# rev_k_v36.net
KiCad netlist of a schematic drawn in EAGLE
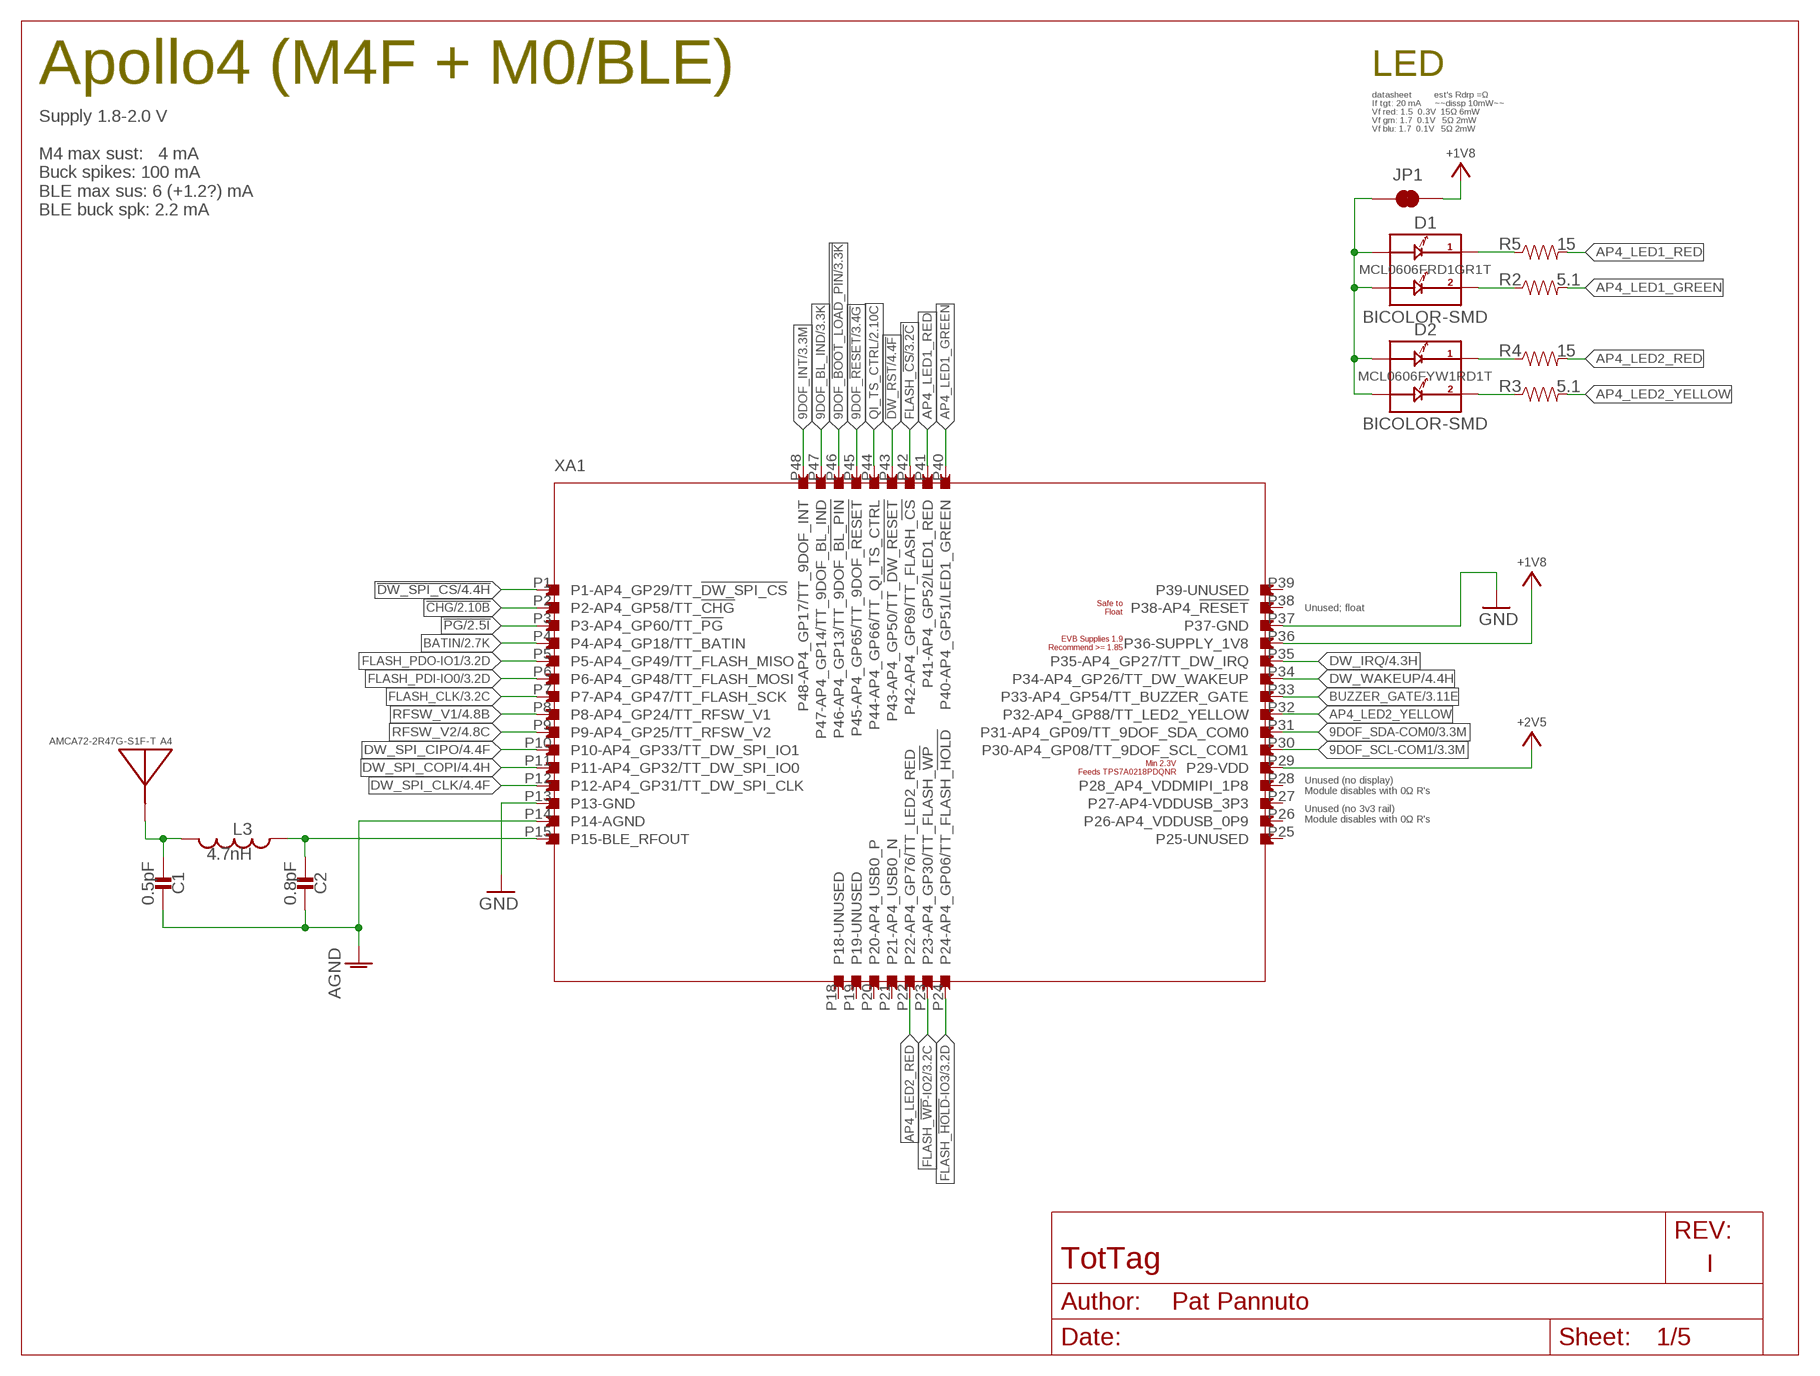
[diagram p0: schematic, sheet 1]
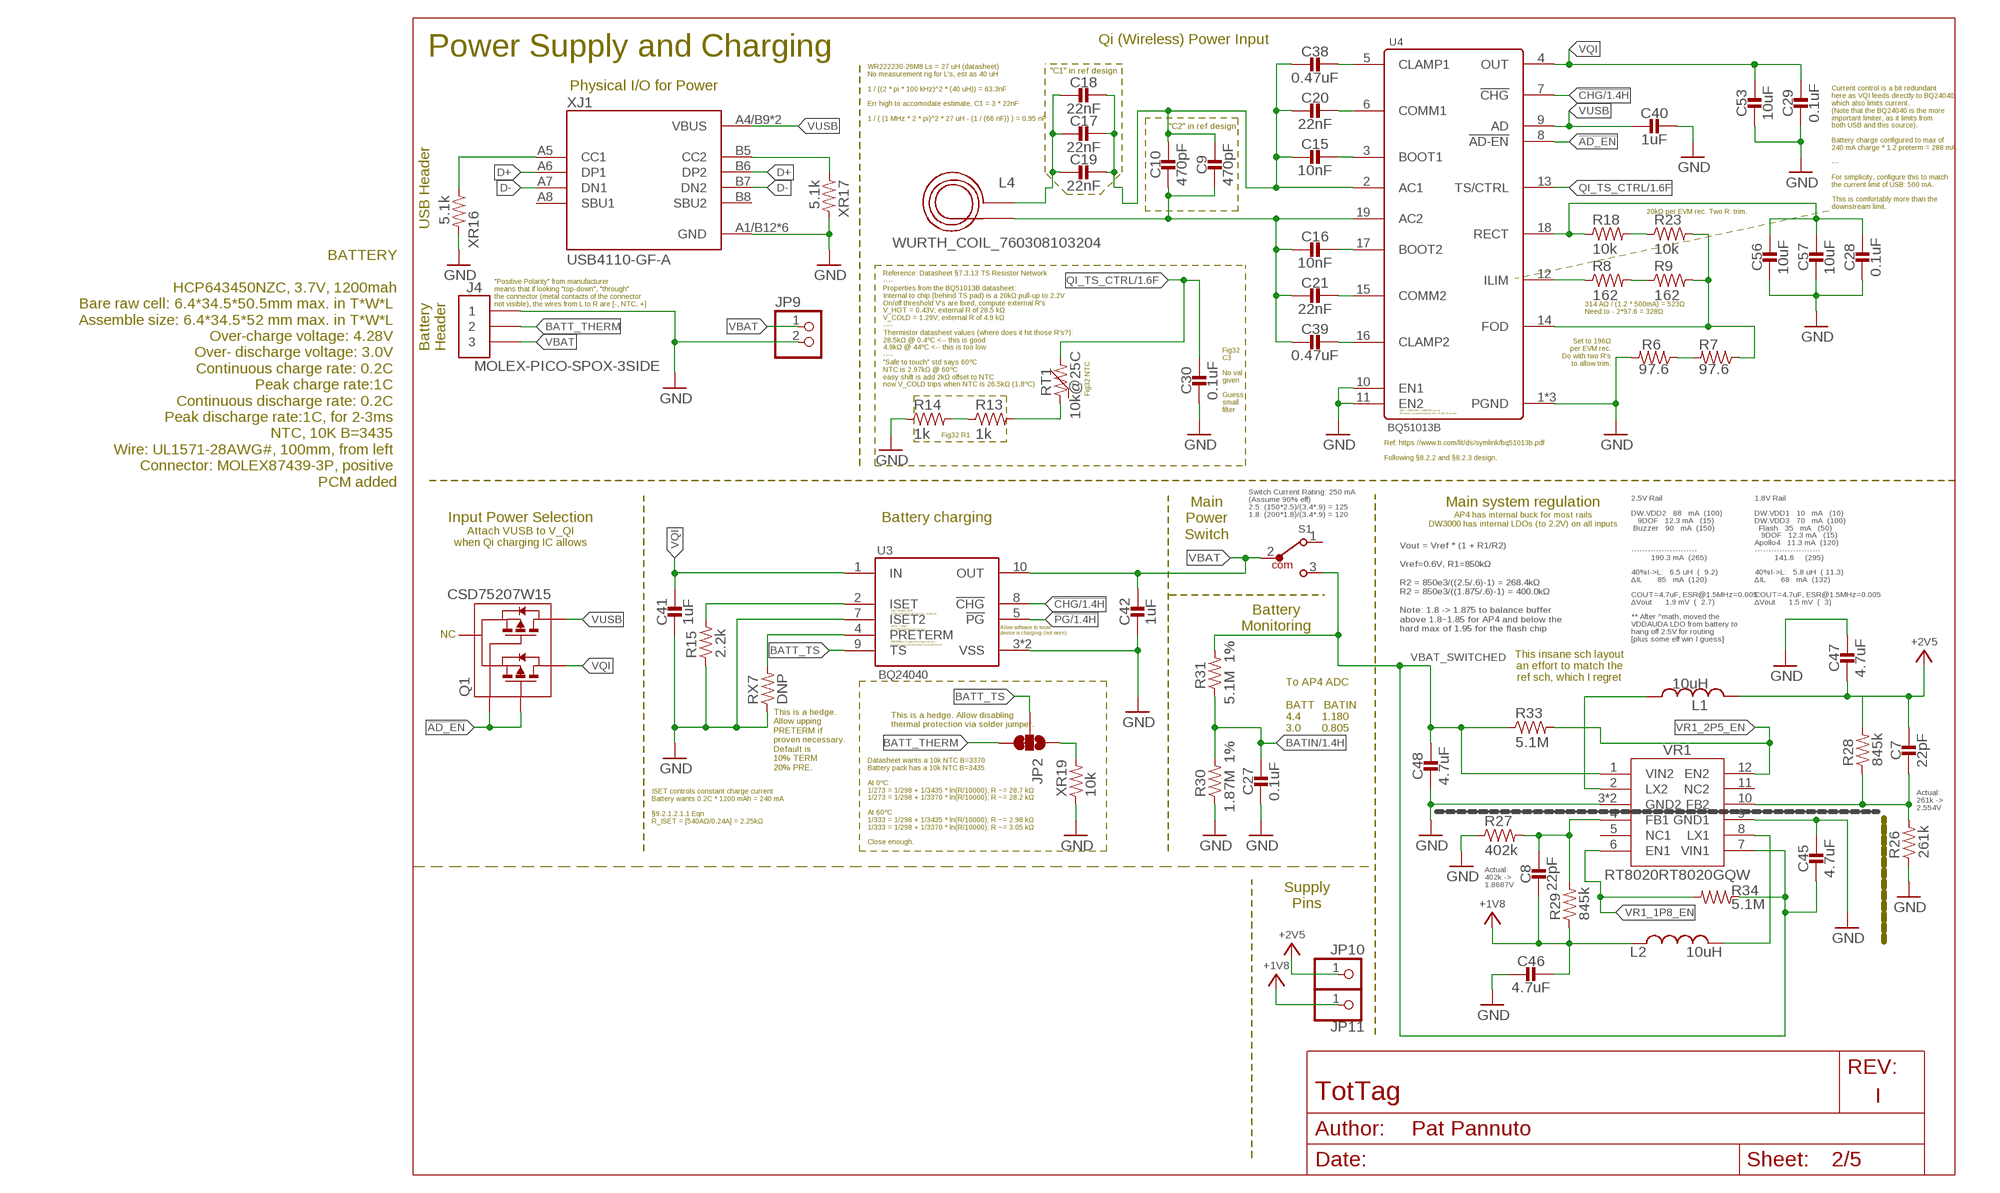
[diagram p1: schematic, sheet 2]
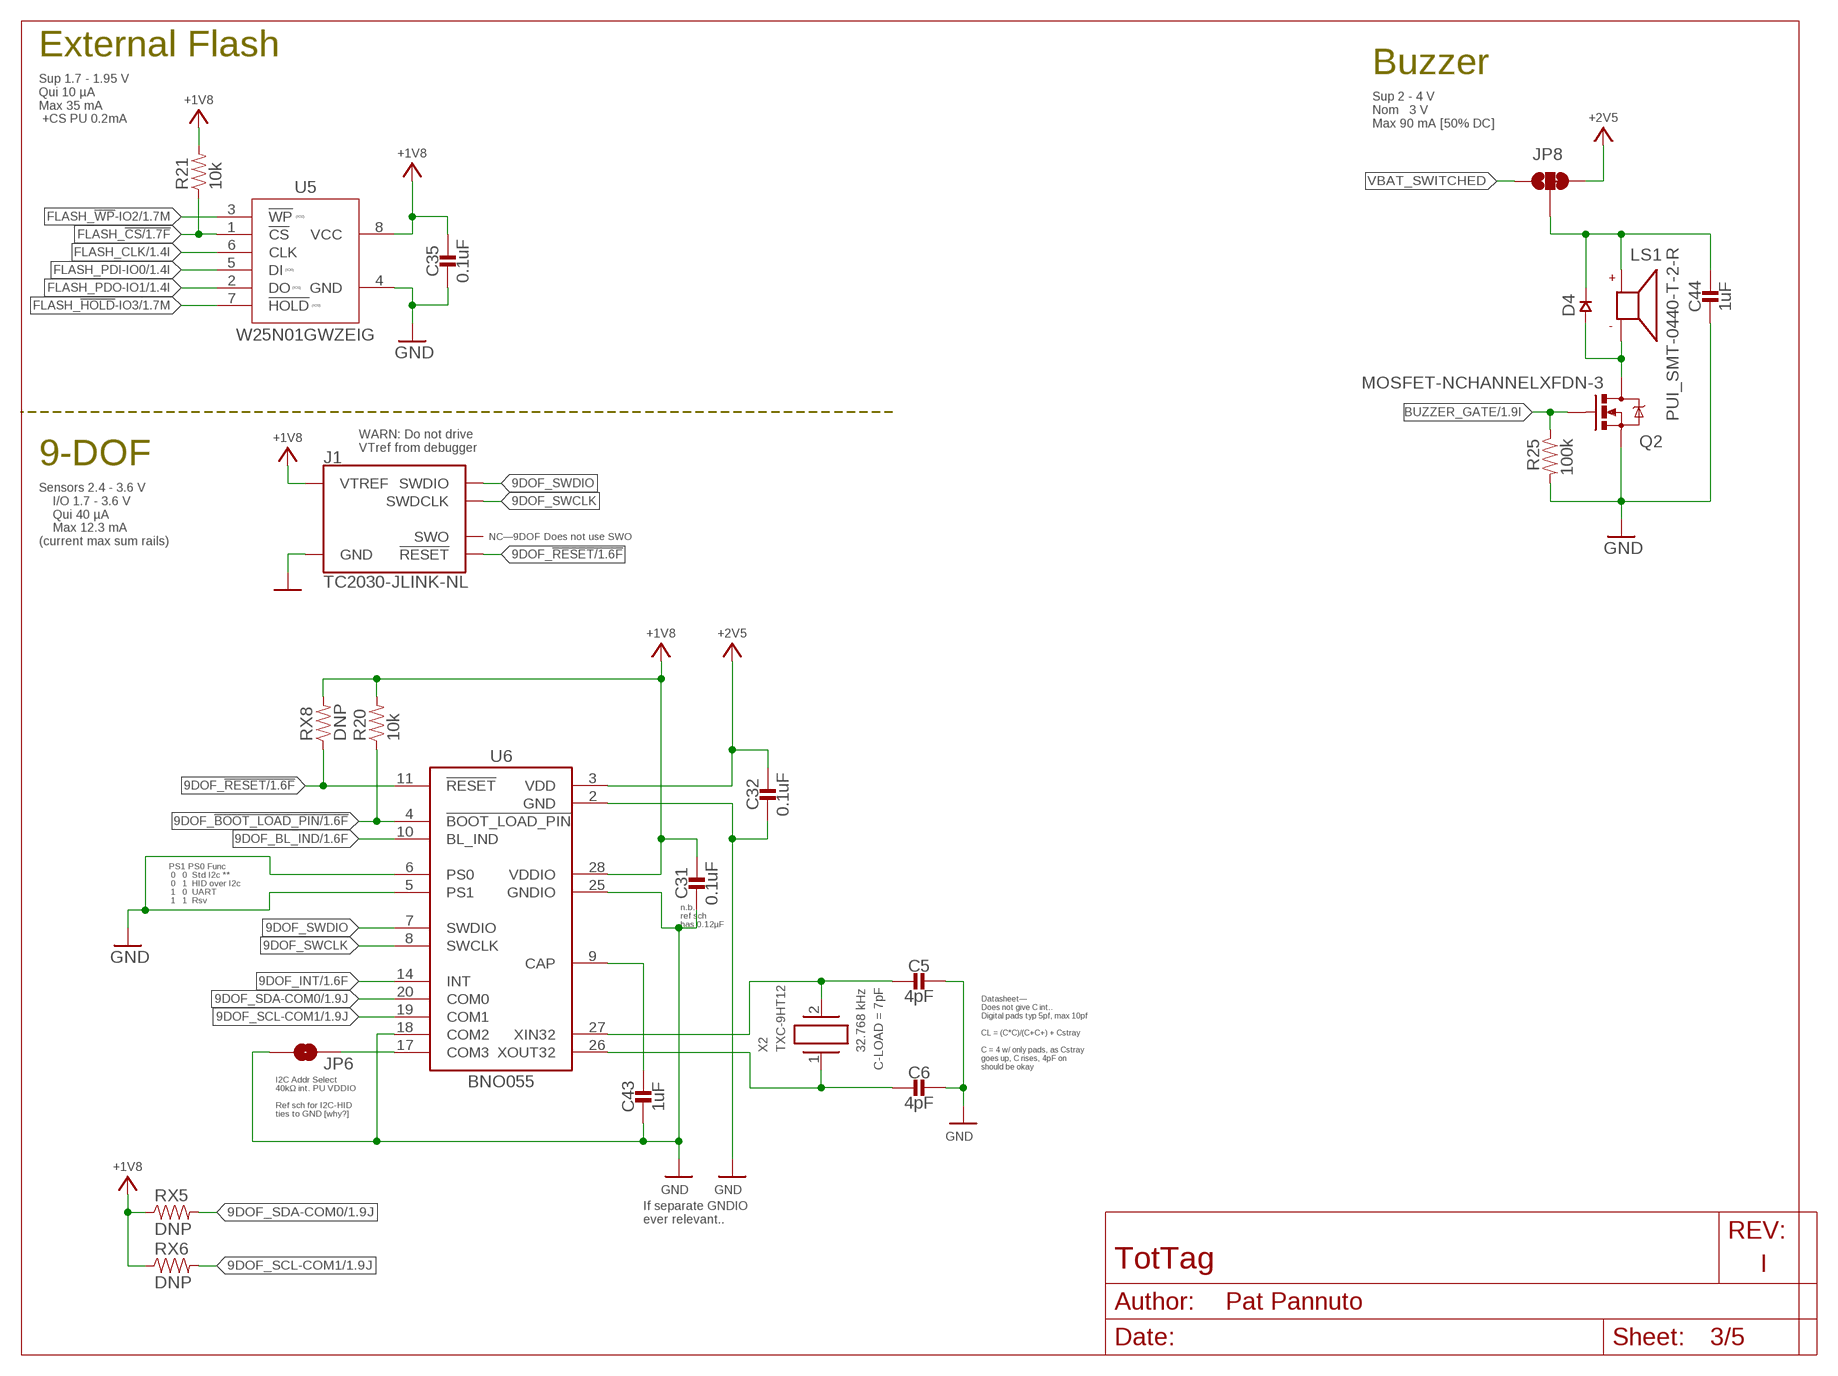
[diagram p2: schematic, sheet 3]
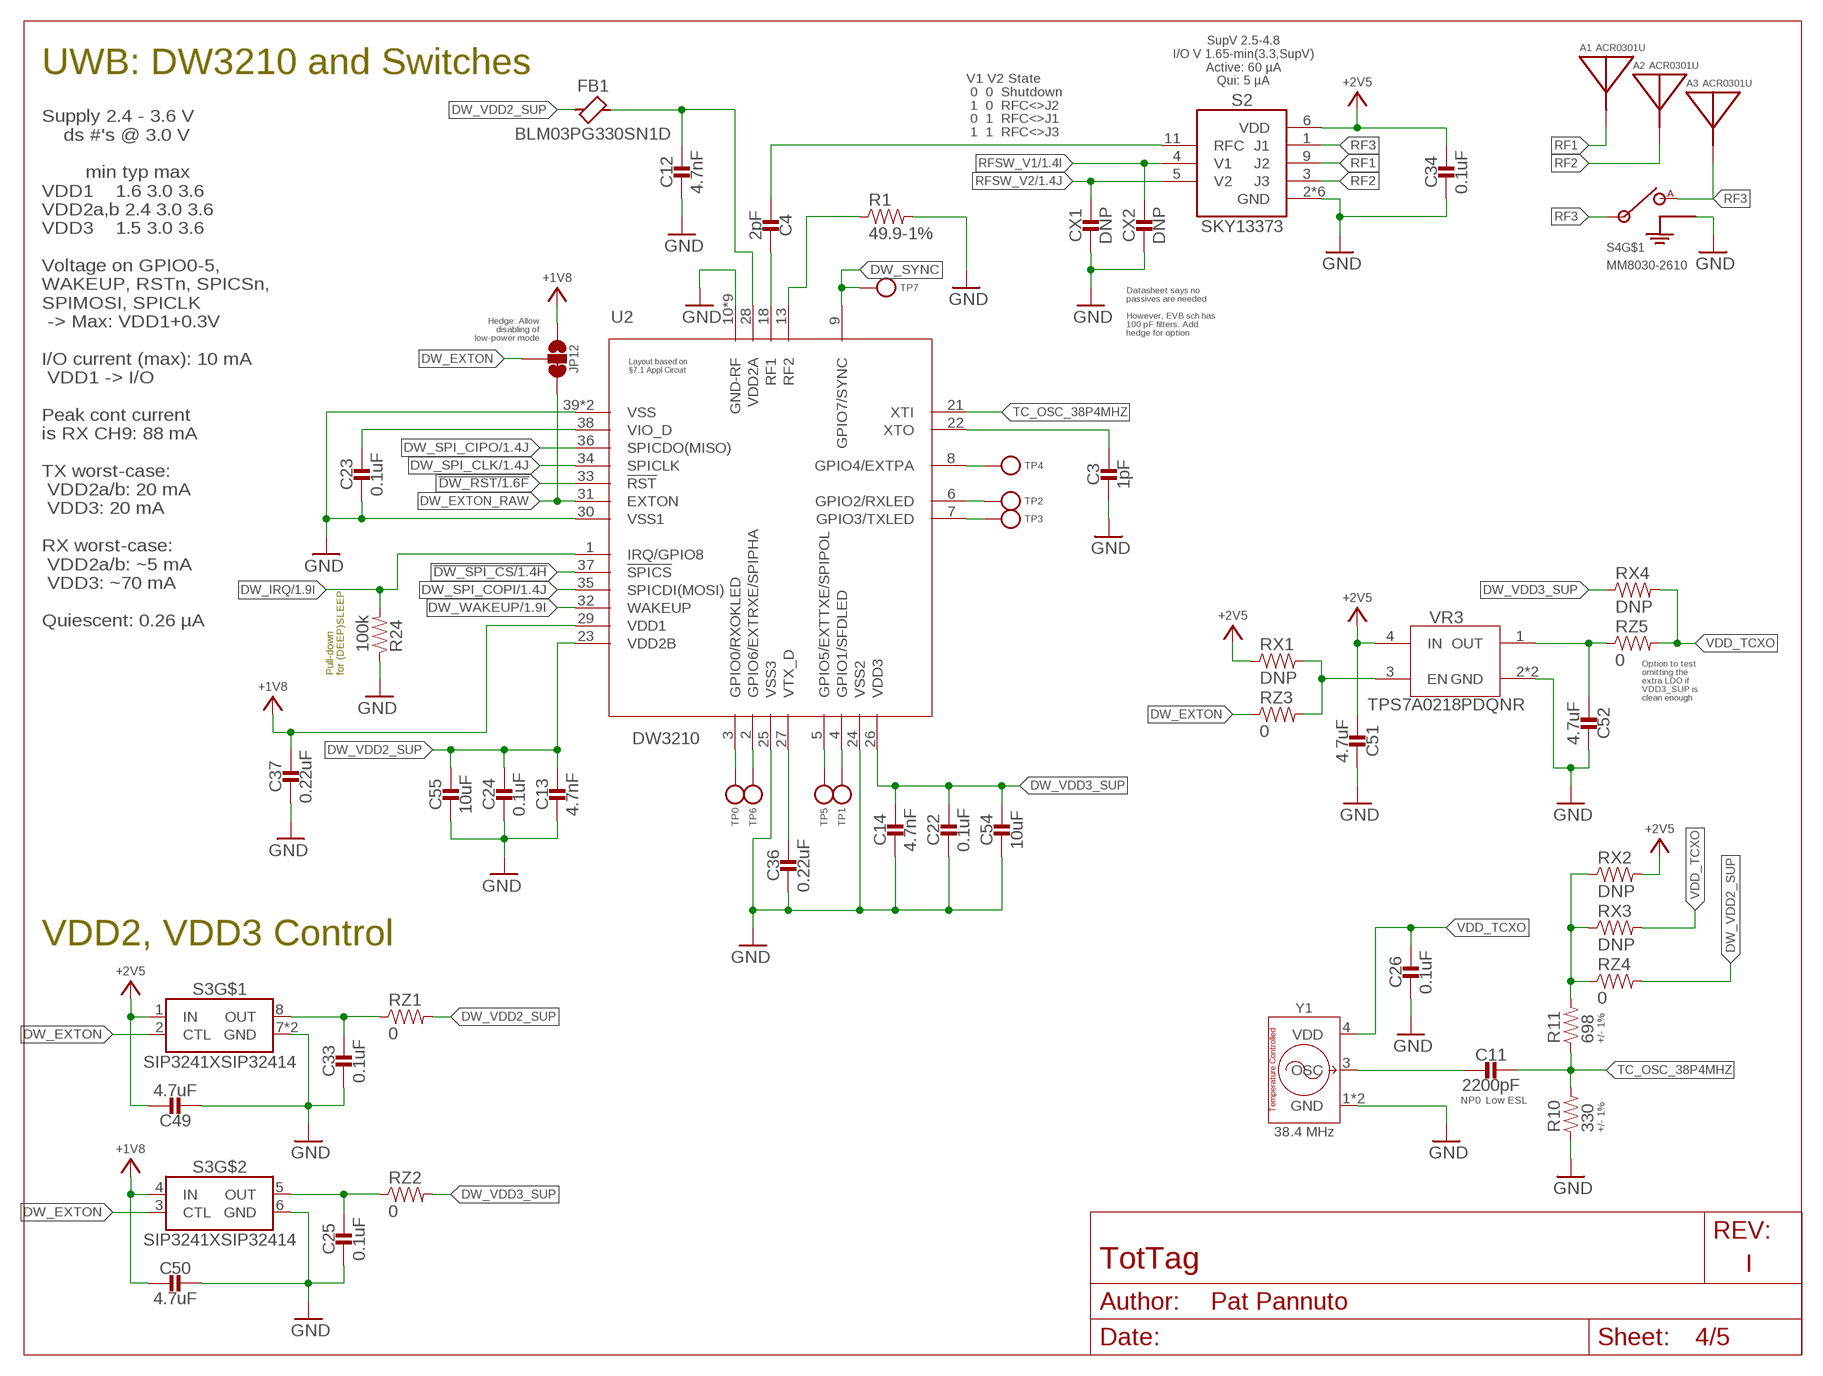
[diagram p3: schematic, sheet 4]
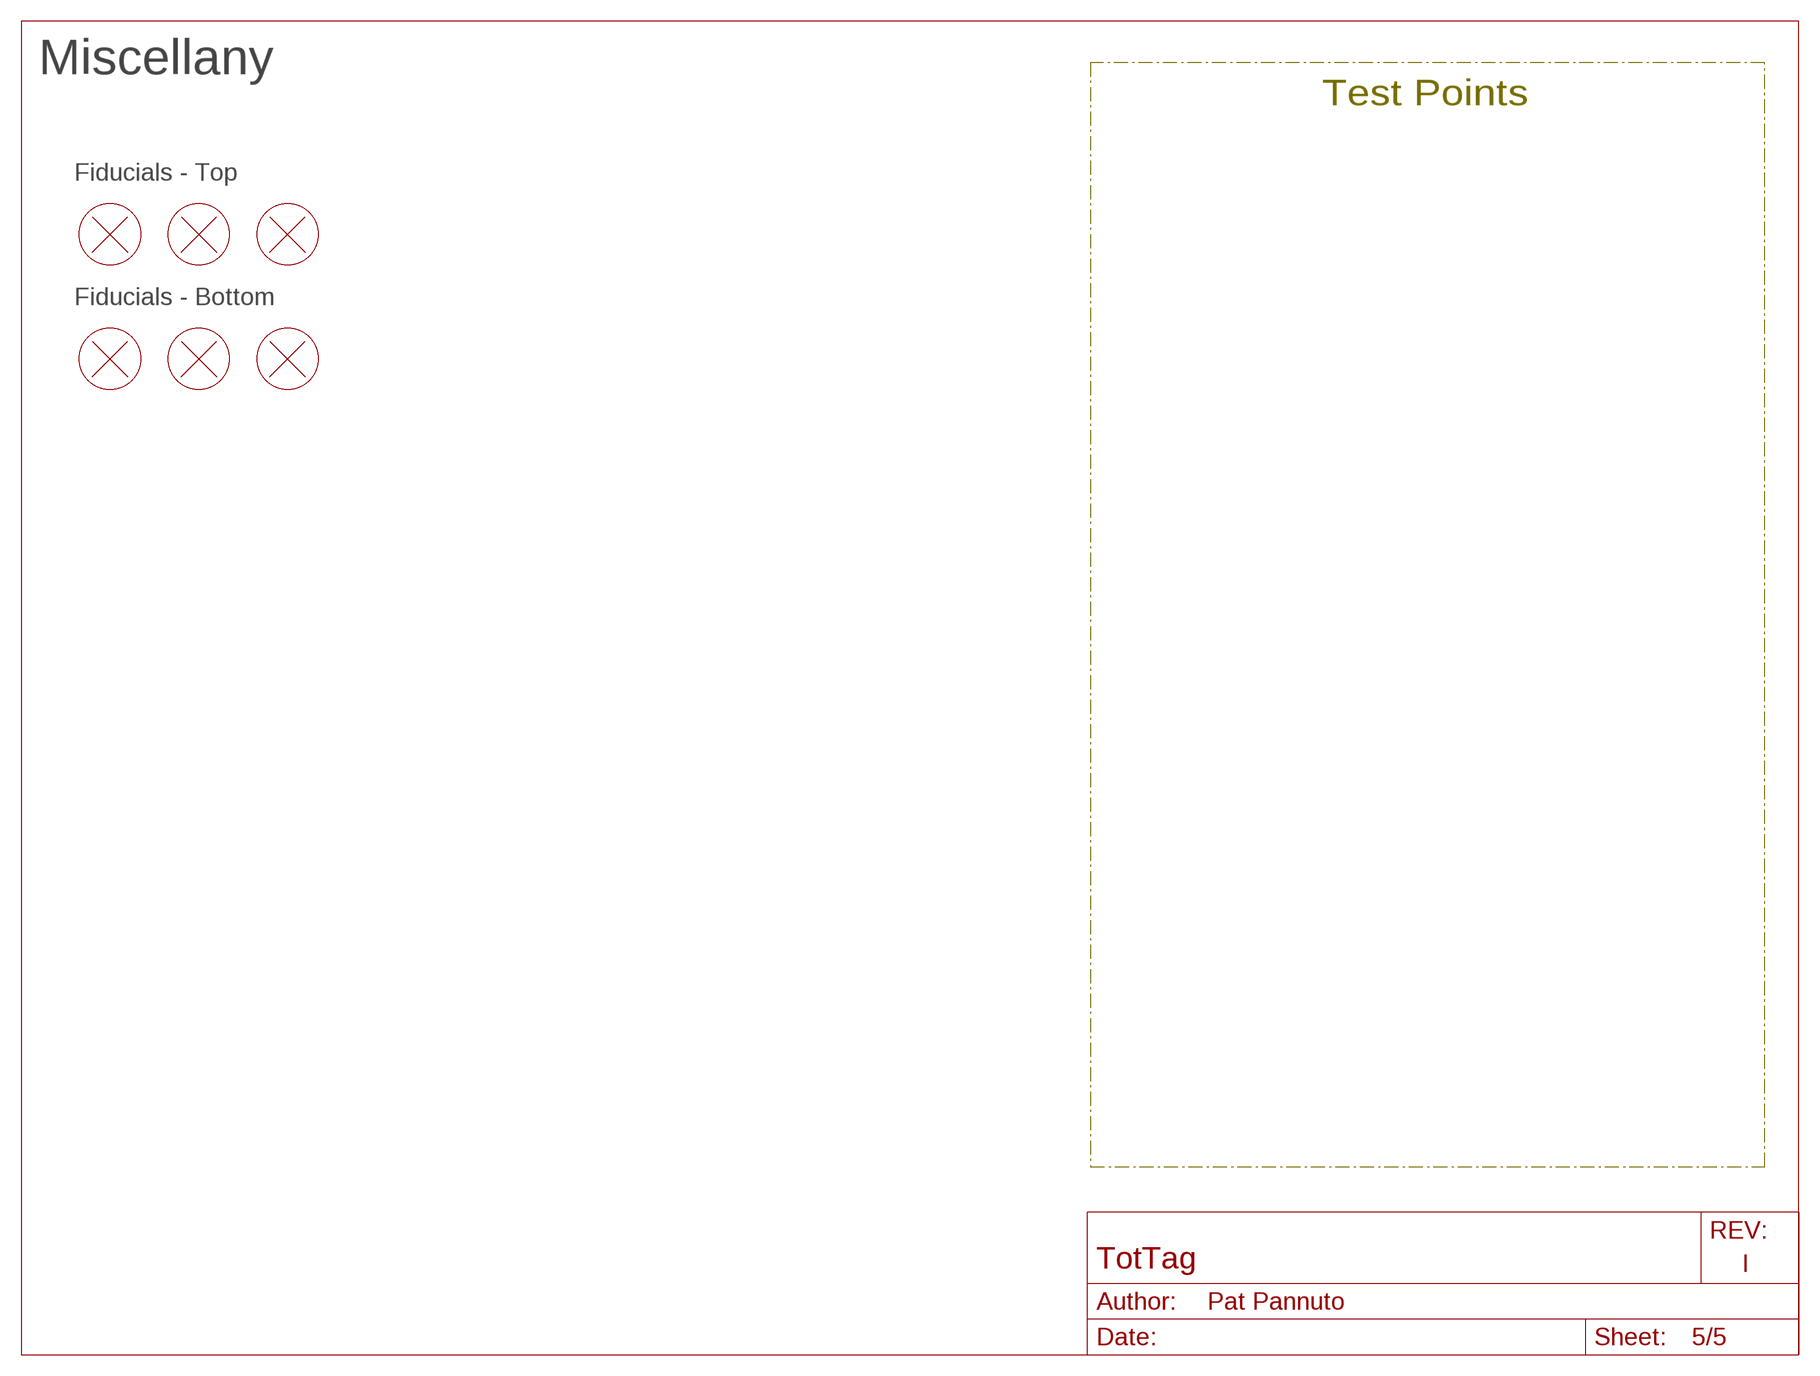
[diagram p4: schematic, sheet 5]

(export (version "E")
  (design (tool "Eeschema 10.0.6"))
  (components
    (comp (ref "FD1")
      (value "FIDUCIAL")
      (footprint "eagle-import:FIDUCIAL_1MM-CU_2MM-MASK")
      (libsource (lib "eagle-import") (part "FIDUCIAL"))
    )
    (comp (ref "FD2")
      (value "FIDUCIAL")
      (footprint "eagle-import:FIDUCIAL_1MM-CU_2MM-MASK")
      (libsource (lib "eagle-import") (part "FIDUCIAL"))
    )
    (comp (ref "FD3")
      (value "FIDUCIAL")
      (footprint "eagle-import:FIDUCIAL_1MM-CU_2MM-MASK")
      (libsource (lib "eagle-import") (part "FIDUCIAL"))
    )
    (comp (ref "FD4")
      (value "FIDUCIAL")
      (footprint "eagle-import:FIDUCIAL_1MM-CU_2MM-MASK")
      (libsource (lib "eagle-import") (part "FIDUCIAL"))
    )
    (comp (ref "FD5")
      (value "FIDUCIAL")
      (footprint "eagle-import:FIDUCIAL_1MM-CU_2MM-MASK")
      (libsource (lib "eagle-import") (part "FIDUCIAL"))
    )
    (comp (ref "FD6")
      (value "FIDUCIAL")
      (footprint "eagle-import:FIDUCIAL_1MM-CU_2MM-MASK")
      (libsource (lib "eagle-import") (part "FIDUCIAL"))
    )
    (comp (ref "C5")
      (value "4pF")
      (footprint "eagle-import:0201_CAP")
      (fields (field (name "MANUFACTURER") "Murata") (field (name "MPN") "GRM0335C1H4R0BA01D"))
      (libsource (lib "eagle-import") (part "passives_20904581_CAPACITOR0201_CAP"))
    )
    (comp (ref "C6")
      (value "4pF")
      (footprint "eagle-import:0201_CAP")
      (fields (field (name "MANUFACTURER") "Murata") (field (name "MPN") "GRM0335C1H4R0BA01D"))
      (libsource (lib "eagle-import") (part "passives_20904581_CAPACITOR0201_CAP"))
    )
    (comp (ref "C31")
      (value "0.1uF")
      (footprint "eagle-import:0402_CAP")
      (fields (field (name "MPN") "CL05A104KP5NNNC"))
      (libsource (lib "eagle-import") (part "passives_20904581_CAPACITOR0402_CAP"))
    )
    (comp (ref "C32")
      (value "0.1uF")
      (footprint "eagle-import:0402_CAP")
      (fields (field (name "MPN") "CL05A104KP5NNNC"))
      (libsource (lib "eagle-import") (part "passives_20904581_CAPACITOR0402_CAP"))
    )
    (comp (ref "C35")
      (value "0.1uF")
      (footprint "eagle-import:0402_CAP")
      (fields (field (name "MPN") "CL05A104KP5NNNC"))
      (libsource (lib "eagle-import") (part "passives_20904581_CAPACITOR0402_CAP"))
    )
    (comp (ref "C43")
      (value "1uF")
      (footprint "eagle-import:0402_CAP")
      (fields (field (name "MPN") "GRM155R70J105KA12J"))
      (libsource (lib "eagle-import") (part "CAPACITOR0402_CAP"))
    )
    (comp (ref "C44")
      (value "1uF")
      (footprint "eagle-import:0402_CAP")
      (fields (field (name "MPN") "GRM155R70J105KA12J"))
      (libsource (lib "eagle-import") (part "CAPACITOR0402_CAP"))
    )
    (comp (ref "D4")
      (value "DIODE0402")
      (footprint "eagle-import:0402_DIODE")
      (fields (field (name "MPN") "CDSQR400B-HF"))
      (libsource (lib "eagle-import") (part "DIODE0402"))
    )
    (comp (ref "J1")
      (value "TC2030-JLINK-NL")
      (footprint "eagle-import:TC2030-IDC-NL")
      (libsource (lib "eagle-import") (part "TC2030-JLINK-NL"))
    )
    (comp (ref "JP6")
      (value "JUMPER-SMT_2_NO_SILK")
      (footprint "eagle-import:SMT-JUMPER_2_NO_SILK")
      (libsource (lib "eagle-import") (part "JUMPER-SMT_2_NO_SILK"))
    )
    (comp (ref "JP8")
      (value "JUMPER-SMT_3_1-NC_TRACE_SILK")
      (footprint "eagle-import:SMT-JUMPER_3_1-NC_TRACE_SILK")
      (libsource (lib "eagle-import") (part "JUMPER-SMT_3_1-NC_TRACE_SILK"))
    )
    (comp (ref "LS1")
      (value "PUI_SMT-0440-T-2-R")
      (footprint "eagle-import:SMT-0440-T-2-R")
      (fields (field (name "MPN") "SMT-0440-T-2-R"))
      (libsource (lib "eagle-import") (part "PUI_SMT-0440-T-2-R"))
    )
    (comp (ref "Q2")
      (value "MOSFET-NCHANNELXFDN-3")
      (footprint "eagle-import:XFDFN-3")
      (libsource (lib "eagle-import") (part "MOSFET-NCHANNELXFDN-3"))
    )
    (comp (ref "R20")
      (value "10k")
      (footprint "eagle-import:0402_RES")
      (fields (field (name "MPN") "RC0402JR-0710KL"))
      (libsource (lib "eagle-import") (part "RESISTOR0402_RES"))
    )
    (comp (ref "R21")
      (value "10k")
      (footprint "eagle-import:0402_RES")
      (fields (field (name "MPN") "RC0402JR-0710KL"))
      (libsource (lib "eagle-import") (part "RESISTOR0402_RES"))
    )
    (comp (ref "R25")
      (value "100k")
      (footprint "eagle-import:0402_RES")
      (fields (field (name "MPN") "RT0402BRE07100KL"))
      (libsource (lib "eagle-import") (part "RESISTOR0402_RES"))
    )
    (comp (ref "RX5")
      (value "DNP")
      (footprint "eagle-import:0603-RES")
      (libsource (lib "eagle-import") (part "passives_20904581_RESISTOR0603_RES"))
    )
    (comp (ref "RX6")
      (value "DNP")
      (footprint "eagle-import:0603-RES")
      (libsource (lib "eagle-import") (part "passives_20904581_RESISTOR0603_RES"))
    )
    (comp (ref "RX8")
      (value "DNP")
      (footprint "eagle-import:0603-RES")
      (libsource (lib "eagle-import") (part "passives_20904581_RESISTOR0603_RES"))
    )
    (comp (ref "U5")
      (value "W25N01GWZEIG")
      (footprint "eagle-import:WSON127P800X600X80-9T430X340N")
      (fields (field (name "MANUFACTURER") "Winbond"))
      (libsource (lib "eagle-import") (part "W25N01GWZEIG"))
    )
    (comp (ref "U6")
      (value "BNO055")
      (footprint "eagle-import:LGA28R0P510X4_5P2X3P8X1")
      (fields (field (name "MANUFACTURER") "Bosch Scientific"))
      (libsource (lib "eagle-import") (part "BNO055"))
    )
    (comp (ref "X2")
      (value "TXC-9HT12")
      (footprint "eagle-import:TXC-9HT12")
      (fields
        (field (name "C-LOAD") "7pF")
        (field (name "FREQUENCY") "32.768 kHz")
        (field (name "MANUFACTURER") "TXC Corp")
        (field (name "MPN") "9HT12-32.768KDZY-T")
      )
      (libsource (lib "eagle-import") (part "TXC-9HT12"))
    )
    (comp (ref "A1")
      (value "ACR0301U")
      (footprint "eagle-import:ACR0301U")
      (fields (field (name "MANUFACTURER") "Abracon"))
      (libsource (lib "eagle-import") (part "ACR0301U"))
    )
    (comp (ref "A2")
      (value "ACR0301U")
      (footprint "eagle-import:ACR0301U")
      (fields (field (name "MANUFACTURER") "Abracon"))
      (libsource (lib "eagle-import") (part "ACR0301U"))
    )
    (comp (ref "A3")
      (value "ACR0301U")
      (footprint "eagle-import:ACR0301U")
      (fields (field (name "MANUFACTURER") "Abracon"))
      (libsource (lib "eagle-import") (part "ACR0301U"))
    )
    (comp (ref "C3")
      (value "1pF")
      (footprint "eagle-import:0603_CAP")
      (fields (field (name "MANUFACTURER") "Kemet") (field (name "MPN") "C0603C109C5GACAUTO"))
      (libsource (lib "eagle-import") (part "passives_20904581_CAPACITOR0603_CAP"))
    )
    (comp (ref "C4")
      (value "2pF")
      (footprint "eagle-import:0201_CAP")
      (fields (field (name "MPN") "CBR02C209A5GAC"))
      (libsource (lib "eagle-import") (part "CAPACITOR0201_CAP"))
    )
    (comp (ref "C11")
      (value "2200pF")
      (footprint "eagle-import:0603_CAP")
      (fields
        (field (name "FEATURE") "Low ESL")
        (field (name "MANUFACTURER") "Kemet")
        (field (name "MPN") "C0603C222F3GEC7867")
        (field (name "TEMPCO") "NP0")
      )
      (libsource (lib "eagle-import") (part "passives_20904581_CAPACITOR0603_CAP"))
    )
    (comp (ref "C12")
      (value "4.7nF")
      (footprint "eagle-import:0402_CAP")
      (fields (field (name "MPN") "C0402C472K3RAC7867"))
      (libsource (lib "eagle-import") (part "CAPACITOR0402_CAP"))
    )
    (comp (ref "C13")
      (value "4.7nF")
      (footprint "eagle-import:0402_CAP")
      (fields (field (name "MPN") "C0402C472K3RAC7867"))
      (libsource (lib "eagle-import") (part "passives_20904581_CAPACITOR0402_CAP"))
    )
    (comp (ref "C14")
      (value "4.7nF")
      (footprint "eagle-import:0402_CAP")
      (fields (field (name "MPN") "C0402C472K3RAC7867"))
      (libsource (lib "eagle-import") (part "CAPACITOR0402_CAP"))
    )
    (comp (ref "C22")
      (value "0.1uF")
      (footprint "eagle-import:0402_CAP")
      (fields (field (name "MPN") "CL05A104KP5NNNC"))
      (libsource (lib "eagle-import") (part "passives_20904581_CAPACITOR0402_CAP"))
    )
    (comp (ref "C23")
      (value "0.1uF")
      (footprint "eagle-import:0402_CAP")
      (fields (field (name "MPN") "CL05A104KP5NNNC"))
      (libsource (lib "eagle-import") (part "passives_20904581_CAPACITOR0402_CAP"))
    )
    (comp (ref "C24")
      (value "0.1uF")
      (footprint "eagle-import:0402_CAP")
      (fields (field (name "MPN") "CL05A104KP5NNNC"))
      (libsource (lib "eagle-import") (part "passives_20904581_CAPACITOR0402_CAP"))
    )
    (comp (ref "C25")
      (value "0.1uF")
      (footprint "eagle-import:0402_CAP")
      (fields (field (name "MPN") "CL05A104KP5NNNC"))
      (libsource (lib "eagle-import") (part "passives_20904581_CAPACITOR0402_CAP"))
    )
    (comp (ref "C26")
      (value "0.1uF")
      (footprint "eagle-import:0402_CAP")
      (fields (field (name "MPN") "CL05A104KP5NNNC"))
      (libsource (lib "eagle-import") (part "passives_20904581_CAPACITOR0402_CAP"))
    )
    (comp (ref "C33")
      (value "0.1uF")
      (footprint "eagle-import:0402_CAP")
      (fields (field (name "MPN") "CL05A104KP5NNNC"))
      (libsource (lib "eagle-import") (part "passives_20904581_CAPACITOR0402_CAP"))
    )
    (comp (ref "C34")
      (value "0.1uF")
      (footprint "eagle-import:0402_CAP")
      (fields (field (name "MPN") "CL05A104KP5NNNC"))
      (libsource (lib "eagle-import") (part "passives_20904581_CAPACITOR0402_CAP"))
    )
    (comp (ref "C36")
      (value "0.22uF")
      (footprint "eagle-import:0402_CAP")
      (fields (field (name "MPN") "CL05A224KP5NNNC"))
      (libsource (lib "eagle-import") (part "CAPACITOR0402_CAP"))
    )
    (comp (ref "C37")
      (value "0.22uF")
      (footprint "eagle-import:0402_CAP")
      (fields (field (name "MPN") "CL05A224KP5NNNC"))
      (libsource (lib "eagle-import") (part "CAPACITOR0402_CAP"))
    )
    (comp (ref "C49")
      (value "4.7uF")
      (footprint "eagle-import:0603_CAP")
      (fields (field (name "MPN") "C1608X7S1A475K080AC"))
      (libsource (lib "eagle-import") (part "passives_20904581_CAPACITOR0603_CAP"))
    )
    (comp (ref "C50")
      (value "4.7uF")
      (footprint "eagle-import:0603_CAP")
      (fields (field (name "MPN") "C1608X7S1A475K080AC"))
      (libsource (lib "eagle-import") (part "passives_20904581_CAPACITOR0603_CAP"))
    )
    (comp (ref "C51")
      (value "4.7uF")
      (footprint "eagle-import:0603_CAP")
      (fields (field (name "MPN") "C1608X7S1A475K080AC"))
      (libsource (lib "eagle-import") (part "passives_20904581_CAPACITOR0603_CAP"))
    )
    (comp (ref "C52")
      (value "4.7uF")
      (footprint "eagle-import:0603_CAP")
      (fields (field (name "MPN") "C1608X7S1A475K080AC"))
      (libsource (lib "eagle-import") (part "passives_20904581_CAPACITOR0603_CAP"))
    )
    (comp (ref "C54")
      (value "10uF")
      (footprint "eagle-import:0603_CAP")
      (fields (field (name "MPN") "CM105X5R106M25AT"))
      (libsource (lib "eagle-import") (part "passives_20904581_CAPACITOR0603_CAP"))
    )
    (comp (ref "C55")
      (value "10uF")
      (footprint "eagle-import:0603_CAP")
      (fields (field (name "MPN") "CM105X5R106M25AT"))
      (libsource (lib "eagle-import") (part "passives_20904581_CAPACITOR0603_CAP"))
    )
    (comp (ref "CX1")
      (value "DNP")
      (footprint "eagle-import:0603_CAP")
      (libsource (lib "eagle-import") (part "passives_20904581_CAPACITOR0603_CAP"))
    )
    (comp (ref "CX2")
      (value "DNP")
      (footprint "eagle-import:0603_CAP")
      (libsource (lib "eagle-import") (part "passives_20904581_CAPACITOR0603_CAP"))
    )
    (comp (ref "FB1")
      (value "BLM03PG330SN1D")
      (footprint "eagle-import:0201_FB")
      (fields (field (name "MANUFACTURER") "Murata"))
      (libsource (lib "eagle-import") (part "FERRITE_BEAD0201"))
    )
    (comp (ref "JP12")
      (value "JUMPER-SMT_3_1-NC_TRACE_SILK")
      (footprint "eagle-import:SMT-JUMPER_3_1-NC_TRACE_SILK")
      (libsource (lib "eagle-import") (part "JUMPER-SMT_3_1-NC_TRACE_SILK"))
    )
    (comp (ref "R1")
      (value "49.9-1%")
      (footprint "eagle-import:0201_RES")
      (fields (field (name "MPN") "ERJ-1GNF49R9C"))
      (libsource (lib "eagle-import") (part "passives_20904581_RESISTOR0201_RES"))
    )
    (comp (ref "R10")
      (value "330")
      (footprint "eagle-import:0603-RES")
      (fields
        (field (name "MANUFACTURER") "Yageo")
        (field (name "MPN") "RC0805FR-13330RL")
        (field (name "TOLERANCE") "+/- 1%")
      )
      (libsource (lib "eagle-import") (part "passives_20904581_RESISTOR0603_RES"))
    )
    (comp (ref "R11")
      (value "698")
      (footprint "eagle-import:0603-RES")
      (fields
        (field (name "MANUFACTURER") "Yageo")
        (field (name "MPN") "RC0805FR-07698RL")
        (field (name "TOLERANCE") "+/- 1%")
      )
      (libsource (lib "eagle-import") (part "passives_20904581_RESISTOR0603_RES"))
    )
    (comp (ref "R24")
      (value "100k")
      (footprint "eagle-import:0402_RES")
      (fields (field (name "MPN") "RT0402BRE07100KL"))
      (libsource (lib "eagle-import") (part "RESISTOR0402_RES"))
    )
    (comp (ref "RX1")
      (value "DNP")
      (footprint "eagle-import:0603-RES")
      (libsource (lib "eagle-import") (part "passives_20904581_RESISTOR0603_RES"))
    )
    (comp (ref "RX2")
      (value "DNP")
      (footprint "eagle-import:0603-RES")
      (libsource (lib "eagle-import") (part "passives_20904581_RESISTOR0603_RES"))
    )
    (comp (ref "RX3")
      (value "DNP")
      (footprint "eagle-import:0603-RES")
      (libsource (lib "eagle-import") (part "passives_20904581_RESISTOR0603_RES"))
    )
    (comp (ref "RX4")
      (value "DNP")
      (footprint "eagle-import:0603-RES")
      (libsource (lib "eagle-import") (part "passives_20904581_RESISTOR0603_RES"))
    )
    (comp (ref "RZ1")
      (value "0")
      (footprint "eagle-import:0603-RES")
      (fields (field (name "MPN") "RMCF0603ZT0R00"))
      (libsource (lib "eagle-import") (part "passives_20904581_RESISTOR0603_RES"))
    )
    (comp (ref "RZ2")
      (value "0")
      (footprint "eagle-import:0603-RES")
      (fields (field (name "MPN") "RMCF0603ZT0R00"))
      (libsource (lib "eagle-import") (part "passives_20904581_RESISTOR0603_RES"))
    )
    (comp (ref "RZ3")
      (value "0")
      (footprint "eagle-import:0603-RES")
      (fields (field (name "MPN") "RMCF0603ZT0R00"))
      (libsource (lib "eagle-import") (part "passives_20904581_RESISTOR0603_RES"))
    )
    (comp (ref "RZ4")
      (value "0")
      (footprint "eagle-import:0603-RES")
      (fields (field (name "MPN") "RMCF0603ZT0R00"))
      (libsource (lib "eagle-import") (part "passives_20904581_RESISTOR0603_RES"))
    )
    (comp (ref "RZ5")
      (value "0")
      (footprint "eagle-import:0603-RES")
      (fields (field (name "MPN") "RMCF0603ZT0R00"))
      (libsource (lib "eagle-import") (part "passives_20904581_RESISTOR0603_RES"))
    )
    (comp (ref "S2")
      (value "SKY13373")
      (footprint "eagle-import:SKY13373")
      (fields (field (name "MANUFACTURER") "Skyworks") (field (name "MPN") "SKY13373-460LF"))
      (libsource (lib "eagle-import") (part "SKY13373"))
    )
    (comp (ref "S3")
      (value "SIP3241XSIP32414")
      (footprint "eagle-import:TDFN2X2X0P6-8")
      (fields (field (name "MANUFACTURER") "Vishay") (field (name "MPN") "SIP32414DNP-T1-GE4"))
      (libsource (lib "eagle-import") (part "SIP3241XSIP32414"))
    )
    (comp (ref "S4")
      (value "MM8030-2610")
      (footprint "eagle-import:MM8030-2610")
      (fields (field (name "MANUFACTURER") "Murata"))
      (libsource (lib "eagle-import") (part "MM8030-2610"))
    )
    (comp (ref "TP0")
      (value "TEST-POINT")
      (footprint "eagle-import:PAD.03X.03")
      (libsource (lib "eagle-import") (part "TEST-POINT"))
    )
    (comp (ref "TP1")
      (value "TEST-POINT")
      (footprint "eagle-import:PAD.03X.03")
      (libsource (lib "eagle-import") (part "TEST-POINT"))
    )
    (comp (ref "TP2")
      (value "TEST-POINT")
      (footprint "eagle-import:PAD.03X.03")
      (libsource (lib "eagle-import") (part "TEST-POINT"))
    )
    (comp (ref "TP3")
      (value "TEST-POINT")
      (footprint "eagle-import:PAD.03X.03")
      (libsource (lib "eagle-import") (part "TEST-POINT"))
    )
    (comp (ref "TP4")
      (value "TEST-POINT")
      (footprint "eagle-import:PAD.03X.03")
      (libsource (lib "eagle-import") (part "TEST-POINT"))
    )
    (comp (ref "TP5")
      (value "TEST-POINT")
      (footprint "eagle-import:PAD.03X.03")
      (libsource (lib "eagle-import") (part "TEST-POINT"))
    )
    (comp (ref "TP6")
      (value "TEST-POINT")
      (footprint "eagle-import:PAD.03X.03")
      (libsource (lib "eagle-import") (part "TEST-POINT"))
    )
    (comp (ref "TP7")
      (value "TEST-POINT")
      (footprint "eagle-import:PAD.03X.03")
      (libsource (lib "eagle-import") (part "TEST-POINT"))
    )
    (comp (ref "U2")
      (value "DW3210")
      (footprint "eagle-import:QFN40P500X500X80-40N")
      (fields (field (name "MANUFACTURER") "Qorvo"))
      (libsource (lib "eagle-import") (part "DW3210"))
    )
    (comp (ref "VR3")
      (value "TPS7A0218PDQNR")
      (footprint "eagle-import:4-XDFN-EP")
      (libsource (lib "eagle-import") (part "TPS7A0218PDQNR"))
    )
    (comp (ref "Y1")
      (value "38.4 MHz")
      (footprint "eagle-import:OSCCC200X160X80")
      (fields (field (name "MANUFACTURER") "Jauch Quartz") (field (name "MPN") "O 38,40-JT21G-E-M-1,8-LF"))
      (libsource (lib "eagle-import") (part "JT21G"))
    )
    (comp (ref "A4")
      (value "AMCA72-2R47G-S1F-T")
      (footprint "eagle-import:AMCA72-2R470G-S1F-T")
      (fields (field (name "MPN") "AMCA72-2R470G-S1F-T4"))
      (libsource (lib "eagle-import") (part "AMCA72-2R47G-S1F-T"))
    )
    (comp (ref "C1")
      (value "0.5pF")
      (footprint "eagle-import:0402_CAP")
      (fields (field (name "MPN") "GJM1555C1HR50WB01D"))
      (libsource (lib "eagle-import") (part "CAPACITOR0402_CAP"))
    )
    (comp (ref "C2")
      (value "0.8pF")
      (footprint "eagle-import:0402_CAP")
      (fields (field (name "MPN") "GJM1555C1HR80WB01D"))
      (libsource (lib "eagle-import") (part "CAPACITOR0402_CAP"))
    )
    (comp (ref "D1")
      (value "BICOLOR-SMD")
      (footprint "eagle-import:LED-0606")
      (fields (field (name "MPN") "MCL0606FRD1GR1T"))
      (libsource (lib "eagle-import") (part "BICOLOR-SMD"))
    )
    (comp (ref "D2")
      (value "BICOLOR-SMD")
      (footprint "eagle-import:LED-0606")
      (fields (field (name "MPN") "MCL0606FYW1RD1T"))
      (libsource (lib "eagle-import") (part "BICOLOR-SMD"))
    )
    (comp (ref "JP1")
      (value "JUMPER-SMT_2_NC_TRACE_SILK")
      (footprint "eagle-import:SMT-JUMPER_2_NC_TRACE_SILK")
      (libsource (lib "eagle-import") (part "JUMPER-SMT_2_NC_TRACE_SILK"))
    )
    (comp (ref "L3")
      (value "4.7nH")
      (footprint "eagle-import:0402_CAP")
      (fields (field (name "MPN") "LQW15AN4N7G8ZD"))
      (libsource (lib "eagle-import") (part "INDUCTOR0402"))
    )
    (comp (ref "R2")
      (value "5.1")
      (footprint "eagle-import:0402_RES")
      (fields (field (name "MPN") "RC0402JR-075R1L"))
      (libsource (lib "eagle-import") (part "RESISTOR0402_RES"))
    )
    (comp (ref "R3")
      (value "5.1")
      (footprint "eagle-import:0402_RES")
      (fields (field (name "MPN") "RC0402JR-075R1L"))
      (libsource (lib "eagle-import") (part "RESISTOR0402_RES"))
    )
    (comp (ref "R4")
      (value "15")
      (footprint "eagle-import:0402_RES")
      (fields (field (name "MPN") "RC0402JR-0715RL"))
      (libsource (lib "eagle-import") (part "RESISTOR0402_RES"))
    )
    (comp (ref "R5")
      (value "15")
      (footprint "eagle-import:0402_RES")
      (fields (field (name "MPN") "RC0402JR-0715RL"))
      (libsource (lib "eagle-import") (part "RESISTOR0402_RES"))
    )
    (comp (ref "XA1")
      (value "APOLLO4_BLUEPLUS_MODULE")
      (footprint "eagle-import:APOLLO4_BLUEPLUS_MODULE")
      (libsource (lib "eagle-import") (part "APOLLO4_BLUEPLUS_MODULE"))
    )
    (comp (ref "C7")
      (value "22pF")
      (footprint "eagle-import:0201_CAP")
      (fields (field (name "MPN") "GRM0335C1H220FA01D"))
      (libsource (lib "eagle-import") (part "passives_20904581_CAPACITOR0201_CAP"))
    )
    (comp (ref "C8")
      (value "22pF")
      (footprint "eagle-import:0201_CAP")
      (fields (field (name "MPN") "GRM0335C1H220FA01D"))
      (libsource (lib "eagle-import") (part "passives_20904581_CAPACITOR0201_CAP"))
    )
    (comp (ref "C9")
      (value "470pF")
      (footprint "eagle-import:0402_CAP")
      (description "CAP CER 470PF 50V C0G/NP0 0402")
      (fields (field (name "MANUFACTURER") "Murata") (field (name "MPN") "GRM1555C1H471JA01J"))
      (libsource (lib "eagle-import") (part "passives_20904581_CAPACITOR0402_CAP"))
    )
    (comp (ref "C10")
      (value "470pF")
      (footprint "eagle-import:0402_CAP")
      (description "CAP CER 470PF 50V C0G/NP0 0402")
      (fields (field (name "MANUFACTURER") "Murata") (field (name "MPN") "GRM1555C1H471JA01J"))
      (libsource (lib "eagle-import") (part "passives_20904581_CAPACITOR0402_CAP"))
    )
    (comp (ref "C15")
      (value "10nF")
      (footprint "eagle-import:0402_CAP")
      (fields (field (name "MPN") "GRM155R71H103KA88J"))
      (libsource (lib "eagle-import") (part "passives_20904581_CAPACITOR0402_CAP"))
    )
    (comp (ref "C16")
      (value "10nF")
      (footprint "eagle-import:0402_CAP")
      (fields (field (name "MPN") "GRM155R71H103KA88J"))
      (libsource (lib "eagle-import") (part "passives_20904581_CAPACITOR0402_CAP"))
    )
    (comp (ref "C17")
      (value "22nF")
      (footprint "eagle-import:0402_CAP")
      (fields (field (name "MPN") "GRM155R71E223JA61D"))
      (libsource (lib "eagle-import") (part "passives_20904581_CAPACITOR0402_CAP"))
    )
    (comp (ref "C18")
      (value "22nF")
      (footprint "eagle-import:0402_CAP")
      (fields (field (name "MPN") "GRM155R71E223JA61D"))
      (libsource (lib "eagle-import") (part "passives_20904581_CAPACITOR0402_CAP"))
    )
    (comp (ref "C19")
      (value "22nF")
      (footprint "eagle-import:0402_CAP")
      (fields (field (name "MPN") "GRM155R71E223JA61D"))
      (libsource (lib "eagle-import") (part "passives_20904581_CAPACITOR0402_CAP"))
    )
    (comp (ref "C20")
      (value "22nF")
      (footprint "eagle-import:0402_CAP")
      (fields (field (name "MPN") "CC0402ZRY5V8BB223"))
      (libsource (lib "eagle-import") (part "passives_20904581_CAPACITOR0402_CAP"))
    )
    (comp (ref "C21")
      (value "22nF")
      (footprint "eagle-import:0402_CAP")
      (fields (field (name "MPN") "CC0402ZRY5V8BB223"))
      (libsource (lib "eagle-import") (part "passives_20904581_CAPACITOR0402_CAP"))
    )
    (comp (ref "C27")
      (value "0.1uF")
      (footprint "eagle-import:0402_CAP")
      (fields (field (name "MPN") "GRM155R71C104KA88J "))
      (libsource (lib "eagle-import") (part "CAPACITOR0402_CAP"))
    )
    (comp (ref "C28")
      (value "0.1uF")
      (footprint "eagle-import:0402_CAP")
      (fields (field (name "MPN") "GRM155R71C104KA88J "))
      (libsource (lib "eagle-import") (part "CAPACITOR0402_CAP"))
    )
    (comp (ref "C29")
      (value "0.1uF")
      (footprint "eagle-import:0402_CAP")
      (fields (field (name "MPN") "GRM155R71C104KA88J "))
      (libsource (lib "eagle-import") (part "CAPACITOR0402_CAP"))
    )
    (comp (ref "C30")
      (value "0.1uF")
      (footprint "eagle-import:0402_CAP")
      (fields (field (name "MPN") "GRM155R71C104KA88J "))
      (libsource (lib "eagle-import") (part "CAPACITOR0402_CAP"))
    )
    (comp (ref "C38")
      (value "0.47uF")
      (footprint "eagle-import:0402_CAP")
      (fields (field (name "MPN") "GRT155R61E474ME01D"))
      (libsource (lib "eagle-import") (part "passives_20904581_CAPACITOR0402_CAP"))
    )
    (comp (ref "C39")
      (value "0.47uF")
      (footprint "eagle-import:0402_CAP")
      (fields (field (name "MPN") "GRT155R61E474ME01D"))
      (libsource (lib "eagle-import") (part "passives_20904581_CAPACITOR0402_CAP"))
    )
    (comp (ref "C40")
      (value "1uF")
      (footprint "eagle-import:0402_CAP")
      (fields (field (name "MPN") "GRM155R70J105KA12J"))
      (libsource (lib "eagle-import") (part "CAPACITOR0402_CAP"))
    )
    (comp (ref "C41")
      (value "1uF")
      (footprint "eagle-import:0402_CAP")
      (fields (field (name "MPN") "GRM155R70J105KA12J"))
      (libsource (lib "eagle-import") (part "CAPACITOR0402_CAP"))
    )
    (comp (ref "C42")
      (value "1uF")
      (footprint "eagle-import:0402_CAP")
      (fields (field (name "MPN") "GRM155R70J105KA12J"))
      (libsource (lib "eagle-import") (part "CAPACITOR0402_CAP"))
    )
    (comp (ref "C45")
      (value "4.7uF")
      (footprint "eagle-import:0603_CAP")
      (fields (field (name "MPN") "C1608X7S1A475K080AC"))
      (libsource (lib "eagle-import") (part "passives_20904581_CAPACITOR0603_CAP"))
    )
    (comp (ref "C46")
      (value "4.7uF")
      (footprint "eagle-import:0603_CAP")
      (fields (field (name "MPN") "C1608X7S1A475K080AC"))
      (libsource (lib "eagle-import") (part "passives_20904581_CAPACITOR0603_CAP"))
    )
    (comp (ref "C47")
      (value "4.7uF")
      (footprint "eagle-import:0603_CAP")
      (fields (field (name "MPN") "C1608X7S1A475K080AC"))
      (libsource (lib "eagle-import") (part "passives_20904581_CAPACITOR0603_CAP"))
    )
    (comp (ref "C48")
      (value "4.7uF")
      (footprint "eagle-import:0603_CAP")
      (fields (field (name "MPN") "C1608X7S1A475K080AC"))
      (libsource (lib "eagle-import") (part "passives_20904581_CAPACITOR0603_CAP"))
    )
    (comp (ref "C53")
      (value "10uF")
      (footprint "eagle-import:0603_CAP")
      (fields (field (name "MPN") "CM105X5R106M25AT"))
      (libsource (lib "eagle-import") (part "passives_20904581_CAPACITOR0603_CAP"))
    )
    (comp (ref "C56")
      (value "10uF")
      (footprint "eagle-import:0603_CAP")
      (fields (field (name "MPN") "CM105X5R106M25AT"))
      (libsource (lib "eagle-import") (part "passives_20904581_CAPACITOR0603_CAP"))
    )
    (comp (ref "C57")
      (value "10uF")
      (footprint "eagle-import:0603_CAP")
      (fields (field (name "MPN") "CM105X5R106M25AT"))
      (libsource (lib "eagle-import") (part "passives_20904581_CAPACITOR0603_CAP"))
    )
    (comp (ref "J4")
      (value "MOLEX-PICO-SPOX-3SIDE")
      (footprint "eagle-import:MOLEX-PICO-SPOX-3_SIDE")
      (libsource (lib "eagle-import") (part "MOLEX-PICO-SPOX-3SIDE"))
    )
    (comp (ref "JP2")
      (value "JUMPER-SMT_3_1-NC_TRACE_SILK")
      (footprint "eagle-import:SMT-JUMPER_3_1-NC_TRACE_SILK")
      (libsource (lib "eagle-import") (part "JUMPER-SMT_3_1-NC_TRACE_SILK"))
    )
    (comp (ref "JP9")
      (value "PINHD-1X2")
      (footprint "eagle-import:1X02")
      (libsource (lib "eagle-import") (part "PINHD-1X2"))
    )
    (comp (ref "JP10")
      (value "PINHD-1X1")
      (footprint "eagle-import:1X01")
      (libsource (lib "eagle-import") (part "PINHD-1X1"))
    )
    (comp (ref "JP11")
      (value "PINHD-1X1")
      (footprint "eagle-import:1X01")
      (libsource (lib "eagle-import") (part "PINHD-1X1"))
    )
    (comp (ref "L1")
      (value "10uH")
      (footprint "eagle-import:NRX3015")
      (fields (field (name "MANUFACTURER") "TAIYO YUDEN") (field (name "MPN") "NR3015T100M"))
      (libsource (lib "eagle-import") (part "INDUCTORNRX3015"))
    )
    (comp (ref "L2")
      (value "10uH")
      (footprint "eagle-import:NRX3015")
      (fields (field (name "MANUFACTURER") "TAIYO YUDEN") (field (name "MPN") "NR3015T100M"))
      (libsource (lib "eagle-import") (part "INDUCTORNRX3015"))
    )
    (comp (ref "L4")
      (value "WURTH_COIL_760308103204")
      (footprint "eagle-import:WURTH_COIL_760308103204")
      (fields (field (name "MANUFACTURER") "Würth Elektronik") (field (name "MPN") "760308103204"))
      (libsource (lib "eagle-import") (part "WURTH_COIL_760308103204"))
    )
    (comp (ref "Q1")
      (value "CSD75207W15")
      (footprint "eagle-import:DSBGA")
      (fields (field (name "MANUFACTURER") "TEXAS INSTRUMENTS"))
      (libsource (lib "eagle-import") (part "CSD75207W15"))
    )
    (comp (ref "R6")
      (value "97.6")
      (footprint "eagle-import:0402_RES")
      (fields (field (name "MPN") "RMCF0402FT97R6"))
      (libsource (lib "eagle-import") (part "passives_20904581_RESISTOR0402_RES"))
    )
    (comp (ref "R7")
      (value "97.6")
      (footprint "eagle-import:0402_RES")
      (fields (field (name "MPN") "RMCF0402FT97R6"))
      (libsource (lib "eagle-import") (part "passives_20904581_RESISTOR0402_RES"))
    )
    (comp (ref "R8")
      (value "162")
      (footprint "eagle-import:0402_RES")
      (fields (field (name "MPN") "RMCF0402FT162R"))
      (libsource (lib "eagle-import") (part "passives_20904581_RESISTOR0402_RES"))
    )
    (comp (ref "R9")
      (value "162")
      (footprint "eagle-import:0402_RES")
      (fields (field (name "MPN") "RMCF0402FT162R"))
      (libsource (lib "eagle-import") (part "passives_20904581_RESISTOR0402_RES"))
    )
    (comp (ref "R13")
      (value "1k")
      (footprint "eagle-import:0402_RES")
      (libsource (lib "eagle-import") (part "RESISTOR0402_RES"))
    )
    (comp (ref "R14")
      (value "1k")
      (footprint "eagle-import:0402_RES")
      (libsource (lib "eagle-import") (part "RESISTOR0402_RES"))
    )
    (comp (ref "R15")
      (value "2.2k")
      (footprint "eagle-import:0402_RES")
      (fields (field (name "MPN") "RMCF0402JT2K20"))
      (libsource (lib "eagle-import") (part "passives_20904581_RESISTOR0402_RES"))
    )
    (comp (ref "R18")
      (value "10k")
      (footprint "eagle-import:0402_RES")
      (fields (field (name "MPN") "RC0402JR-0710KL"))
      (libsource (lib "eagle-import") (part "RESISTOR0402_RES"))
    )
    (comp (ref "R23")
      (value "10k")
      (footprint "eagle-import:0402_RES")
      (fields (field (name "MPN") "RC0402JR-0710KL"))
      (libsource (lib "eagle-import") (part "RESISTOR0402_RES"))
    )
    (comp (ref "R26")
      (value "261k")
      (footprint "eagle-import:0201_RES")
      (fields (field (name "MPN") "ERJ-1GNF2613C"))
      (libsource (lib "eagle-import") (part "passives_20904581_RESISTOR0201_RES"))
    )
    (comp (ref "R27")
      (value "402k")
      (footprint "eagle-import:0201_RES")
      (fields (field (name "MPN") "ERJ-1GNF4023C"))
      (libsource (lib "eagle-import") (part "passives_20904581_RESISTOR0201_RES"))
    )
    (comp (ref "R28")
      (value "845k")
      (footprint "eagle-import:0201_RES")
      (fields (field (name "MPN") "ERJ-1GNF8453C"))
      (libsource (lib "eagle-import") (part "passives_20904581_RESISTOR0201_RES"))
    )
    (comp (ref "R29")
      (value "845k")
      (footprint "eagle-import:0201_RES")
      (fields (field (name "MPN") "ERJ-1GNF8453C"))
      (libsource (lib "eagle-import") (part "passives_20904581_RESISTOR0201_RES"))
    )
    (comp (ref "R30")
      (value "1.87M")
      (footprint "eagle-import:0402_RES")
      (fields (field (name "MPN") "RMCF0402FT1M87") (field (name "TOLERANCE") "1%"))
      (libsource (lib "eagle-import") (part "RESISTOR0402_RES"))
    )
    (comp (ref "R31")
      (value "5.1M")
      (footprint "eagle-import:0402_RES")
      (fields (field (name "MPN") "RMCF0402FT5M10") (field (name "TOLERANCE") "1%"))
      (libsource (lib "eagle-import") (part "RESISTOR0402_RES"))
    )
    (comp (ref "R33")
      (value "5.1M")
      (footprint "eagle-import:0402_RES")
      (fields (field (name "MPN") "RMCF0402FT5M10"))
      (libsource (lib "eagle-import") (part "RESISTOR0402_RES"))
    )
    (comp (ref "R34")
      (value "5.1M")
      (footprint "eagle-import:0402_RES")
      (fields (field (name "MPN") "RMCF0402FT5M10"))
      (libsource (lib "eagle-import") (part "RESISTOR0402_RES"))
    )
    (comp (ref "RT1")
      (value "10k@25C")
      (footprint "eagle-import:0402_RES")
      (fields (field (name "MPN") "NCU15XH103F60RC"))
      (libsource (lib "eagle-import") (part "THERMISTOR0402"))
    )
    (comp (ref "RX7")
      (value "DNP")
      (footprint "eagle-import:0402_RES")
      (libsource (lib "eagle-import") (part "passives_20904581_RESISTOR0402_RES"))
    )
    (comp (ref "S1")
      (value "450404015514")
      (footprint "eagle-import:450404015514")
      (libsource (lib "eagle-import") (part "450404015514"))
    )
    (comp (ref "U3")
      (value "BQ24040")
      (footprint "eagle-import:DSQ0010A")
      (fields (field (name "MPN") "BQ24040DSQR"))
      (libsource (lib "eagle-import") (part "BQ24040"))
    )
    (comp (ref "U4")
      (value "BQ51013B")
      (footprint "eagle-import:RHL0020A")
      (fields (field (name "MPN") "BQ51013BRHLR"))
      (libsource (lib "eagle-import") (part "BQ51013B"))
    )
    (comp (ref "VR1")
      (value "RT8020RT8020GQW")
      (footprint "eagle-import:SON45P300X300X80-13T160X250N")
      (fields (field (name "MANUFACTURER") "RichTek") (field (name "MPN") "RT8020GQW"))
      (libsource (lib "eagle-import") (part "RT8020RT8020GQW"))
    )
    (comp (ref "XJ1")
      (value "USB4110-GF-A")
      (footprint "eagle-import:GCT_USB4110-GF-A")
      (fields (field (name "MF") "GCT"))
      (libsource (lib "eagle-import") (part "USB4110-GF-A"))
    )
    (comp (ref "XR16")
      (value "5.1k")
      (footprint "eagle-import:0402_RES")
      (fields (field (name "MPN") "RMCF0402FT5K10"))
      (libsource (lib "eagle-import") (part "passives_20904581_RESISTOR0402_RES"))
    )
    (comp (ref "XR17")
      (value "5.1k")
      (footprint "eagle-import:0402_RES")
      (fields (field (name "MPN") "RMCF0402FT5K10"))
      (libsource (lib "eagle-import") (part "passives_20904581_RESISTOR0402_RES"))
    )
    (comp (ref "XR19")
      (value "10k")
      (footprint "eagle-import:0402_RES")
      (fields (field (name "MPN") "RC0402JR-0710KL"))
      (libsource (lib "eagle-import") (part "RESISTOR0402_RES"))
    )
  )
  (nets
    (net (code "1") (name "+1V8") (class "Default")
      (node (ref "C31") (pin "1") (pinfunction "1_1") (pintype "bidirectional"))
      (node (ref "C35") (pin "1") (pinfunction "1_1") (pintype "bidirectional"))
      (node (ref "C37") (pin "1") (pinfunction "1_1") (pintype "bidirectional"))
      (node (ref "C46") (pin "1") (pinfunction "1_1") (pintype "bidirectional"))
      (node (ref "C50") (pin "2") (pinfunction "2_2") (pintype "bidirectional"))
      (node (ref "C8") (pin "P$2") (pinfunction "2_P$2") (pintype "bidirectional"))
      (node (ref "J1") (pin "1") (pinfunction "VTREF_1") (pintype "bidirectional"))
      (node (ref "JP1") (pin "2") (pinfunction "2_2") (pintype "passive"))
      (node (ref "JP11") (pin "1") (pinfunction "1_1") (pintype "passive"))
      (node (ref "JP12") (pin "1") (pinfunction "1_1") (pintype "passive"))
      (node (ref "L2") (pin "P$1") (pinfunction "1_P$1") (pintype "bidirectional"))
      (node (ref "R20") (pin "2") (pinfunction "2_2") (pintype "passive"))
      (node (ref "R21") (pin "2") (pinfunction "2_2") (pintype "passive"))
      (node (ref "R29") (pin "1") (pinfunction "1_1") (pintype "passive"))
      (node (ref "RX5") (pin "1") (pinfunction "1_1") (pintype "passive"))
      (node (ref "RX6") (pin "1") (pinfunction "1_1") (pintype "passive"))
      (node (ref "RX8") (pin "2") (pinfunction "2_2") (pintype "passive"))
      (node (ref "S3") (pin "4") (pinfunction "IN_4") (pintype "bidirectional"))
      (node (ref "U2") (pin "29") (pinfunction "VDD1_29") (pintype "bidirectional"))
      (node (ref "U5") (pin "8") (pinfunction "VCC_8") (pintype "bidirectional"))
      (node (ref "U6") (pin "28") (pinfunction "VDDIO_28") (pintype "bidirectional"))
      (node (ref "XA1") (pin "P36") (pinfunction "P36-SUPPLY_1V8_P36") (pintype "bidirectional"))
    )
    (net (code "2") (name "+2V5") (class "Default")
      (node (ref "C32") (pin "1") (pinfunction "1_1") (pintype "bidirectional"))
      (node (ref "C34") (pin "1") (pinfunction "1_1") (pintype "bidirectional"))
      (node (ref "C47") (pin "2") (pinfunction "2_2") (pintype "bidirectional"))
      (node (ref "C49") (pin "1") (pinfunction "1_1") (pintype "bidirectional"))
      (node (ref "C51") (pin "2") (pinfunction "2_2") (pintype "bidirectional"))
      (node (ref "C7") (pin "P$1") (pinfunction "1_P$1") (pintype "bidirectional"))
      (node (ref "JP10") (pin "1") (pinfunction "1_1") (pintype "passive"))
      (node (ref "JP8") (pin "3") (pinfunction "3_3") (pintype "passive"))
      (node (ref "L1") (pin "P$2") (pinfunction "2_P$2") (pintype "bidirectional"))
      (node (ref "R28") (pin "2") (pinfunction "2_2") (pintype "passive"))
      (node (ref "RX1") (pin "1") (pinfunction "1_1") (pintype "passive"))
      (node (ref "RX2") (pin "2") (pinfunction "2_2") (pintype "passive"))
      (node (ref "S2") (pin "6") (pinfunction "VDD_6") (pintype "power_in"))
      (node (ref "S3") (pin "1") (pinfunction "IN_1") (pintype "bidirectional"))
      (node (ref "U6") (pin "3") (pinfunction "VDD_3") (pintype "bidirectional"))
      (node (ref "VR3") (pin "4") (pinfunction "IN_4") (pintype "bidirectional"))
      (node (ref "XA1") (pin "P29") (pinfunction "P29-VDD_P29") (pintype "bidirectional"))
    )
    (net (code "3") (name "9DOF_BL_IND") (class "Default")
      (node (ref "U6") (pin "10") (pinfunction "BL_IND_10") (pintype "output"))
      (node (ref "XA1") (pin "P47") (pinfunction "P47-AP4_GP14/TT_9DOF_BL_IND_P47") (pintype "bidirectional"))
    )
    (net (code "4") (name "9DOF_INT") (class "Default")
      (node (ref "U6") (pin "14") (pinfunction "INT_14") (pintype "output"))
      (node (ref "XA1") (pin "P48") (pinfunction "P48-AP4_GP17/TT_9DOF_INT_P48") (pintype "bidirectional"))
    )
    (net (code "5") (name "9DOF_SCL-COM1") (class "Default")
      (node (ref "RX6") (pin "2") (pinfunction "2_2") (pintype "passive"))
      (node (ref "U6") (pin "19") (pinfunction "COM1_19") (pintype "bidirectional"))
      (node (ref "XA1") (pin "P30") (pinfunction "P30-AP4_GP08/TT_9DOF_SCL_COM1_P30") (pintype "bidirectional"))
    )
    (net (code "6") (name "9DOF_SDA-COM0") (class "Default")
      (node (ref "RX5") (pin "2") (pinfunction "2_2") (pintype "passive"))
      (node (ref "U6") (pin "20") (pinfunction "COM0_20") (pintype "bidirectional"))
      (node (ref "XA1") (pin "P31") (pinfunction "P31-AP4_GP09/TT_9DOF_SDA_COM0_P31") (pintype "bidirectional"))
    )
    (net (code "7") (name "9DOF_SWCLK") (class "Default")
      (node (ref "J1") (pin "4") (pinfunction "SWDCLK_4") (pintype "bidirectional"))
      (node (ref "U6") (pin "8") (pinfunction "SWCLK_8") (pintype "input"))
    )
    (net (code "8") (name "9DOF_SWDIO") (class "Default")
      (node (ref "J1") (pin "2") (pinfunction "SWDIO_2") (pintype "bidirectional"))
      (node (ref "U6") (pin "7") (pinfunction "SWDIO_7") (pintype "bidirectional"))
    )
    (net (code "9") (name "9DOF_~{BOOT_LOAD_PIN}") (class "Default")
      (node (ref "R20") (pin "1") (pinfunction "1_1") (pintype "passive"))
      (node (ref "U6") (pin "4") (pinfunction "~{BOOT_LOAD_PIN}_4") (pintype "input"))
      (node (ref "XA1") (pin "P46") (pinfunction "P46-AP4_GP13/TT_9DOF_~{BL_PIN}_P46") (pintype "bidirectional"))
    )
    (net (code "10") (name "9DOF_~{RESET}") (class "Default")
      (node (ref "J1") (pin "3") (pinfunction "~{RESET}_3") (pintype "bidirectional"))
      (node (ref "RX8") (pin "1") (pinfunction "1_1") (pintype "passive"))
      (node (ref "U6") (pin "11") (pinfunction "~{RESET}_11") (pintype "bidirectional"))
      (node (ref "XA1") (pin "P45") (pinfunction "P45-AP4_GP65/TT_9DOF_~{RESET}_P45") (pintype "bidirectional"))
    )
    (net (code "11") (name "AGND") (class "Default")
      (node (ref "C1") (pin "2") (pinfunction "2_2") (pintype "bidirectional"))
      (node (ref "C2") (pin "2") (pinfunction "2_2") (pintype "bidirectional"))
      (node (ref "XA1") (pin "P14") (pinfunction "P14-AGND_P14") (pintype "bidirectional"))
    )
    (net (code "12") (name "AP4_LED1_GREEN") (class "Default")
      (node (ref "R2") (pin "2") (pinfunction "2_2") (pintype "passive"))
      (node (ref "XA1") (pin "P40") (pinfunction "P40-AP4_GP51/LED1_GREEN_P40") (pintype "bidirectional"))
    )
    (net (code "13") (name "AP4_LED1_RED") (class "Default")
      (node (ref "R5") (pin "2") (pinfunction "2_2") (pintype "passive"))
      (node (ref "XA1") (pin "P41") (pinfunction "P41-AP4_GP52/LED1_RED_P41") (pintype "bidirectional"))
    )
    (net (code "14") (name "AP4_LED2_RED") (class "Default")
      (node (ref "R4") (pin "2") (pinfunction "2_2") (pintype "passive"))
      (node (ref "XA1") (pin "P22") (pinfunction "P22-AP4_GP76/TT_LED2_RED_P22") (pintype "bidirectional"))
    )
    (net (code "15") (name "AP4_LED2_YELLOW") (class "Default")
      (node (ref "R3") (pin "2") (pinfunction "2_2") (pintype "passive"))
      (node (ref "XA1") (pin "P32") (pinfunction "P32-AP4_GP88/TT_LED2_YELLOW_P32") (pintype "bidirectional"))
    )
    (net (code "16") (name "BATIN") (class "Default")
      (node (ref "C27") (pin "1") (pinfunction "1_1") (pintype "bidirectional"))
      (node (ref "R30") (pin "2") (pinfunction "2_2") (pintype "passive"))
      (node (ref "R31") (pin "1") (pinfunction "1_1") (pintype "passive"))
      (node (ref "XA1") (pin "P4") (pinfunction "P4-AP4_GP18/TT_BATIN_P4") (pintype "bidirectional"))
    )
    (net (code "17") (name "BATT_THERM") (class "Default")
      (node (ref "J4") (pin "2") (pinfunction "2_2") (pintype "bidirectional"))
      (node (ref "J4") (pin "2SUPP") (pinfunction "2_2SUPP") (pintype "bidirectional"))
      (node (ref "JP2") (pin "3") (pinfunction "3_3") (pintype "passive"))
    )
    (net (code "18") (name "BATT_TS") (class "Default")
      (node (ref "JP2") (pin "2") (pinfunction "2_2") (pintype "passive"))
      (node (ref "U3") (pin "9") (pinfunction "TS_9") (pintype "bidirectional"))
    )
    (net (code "19") (name "BUZZER_GATE") (class "Default")
      (node (ref "Q2") (pin "G") (pinfunction "G_G") (pintype "passive"))
      (node (ref "R25") (pin "1") (pinfunction "1_1") (pintype "passive"))
      (node (ref "XA1") (pin "P33") (pinfunction "P33-AP4_GP54/TT_BUZZER_GATE_P33") (pintype "bidirectional"))
    )
    (net (code "20") (name "D+") (class "Default")
      (node (ref "XJ1") (pin "A6") (pinfunction "DP1_A6") (pintype "bidirectional"))
      (node (ref "XJ1") (pin "B6") (pinfunction "DP2_B6") (pintype "bidirectional"))
    )
    (net (code "21") (name "D-") (class "Default")
      (node (ref "XJ1") (pin "A7") (pinfunction "DN1_A7") (pintype "bidirectional"))
      (node (ref "XJ1") (pin "B7") (pinfunction "DN2_B7") (pintype "bidirectional"))
    )
    (net (code "22") (name "DW_EXTON") (class "Default")
      (node (ref "JP12") (pin "2") (pinfunction "2_2") (pintype "passive"))
      (node (ref "RZ3") (pin "1") (pinfunction "1_1") (pintype "passive"))
      (node (ref "S3") (pin "2") (pinfunction "CTL_2") (pintype "bidirectional"))
      (node (ref "S3") (pin "3") (pinfunction "CTL_3") (pintype "bidirectional"))
    )
    (net (code "23") (name "DW_EXTON_RAW") (class "Default")
      (node (ref "JP12") (pin "3") (pinfunction "3_3") (pintype "passive"))
      (node (ref "U2") (pin "31") (pinfunction "EXTON_31") (pintype "bidirectional"))
    )
    (net (code "24") (name "DW_IRQ") (class "Default")
      (node (ref "R24") (pin "2") (pinfunction "2_2") (pintype "passive"))
      (node (ref "U2") (pin "1") (pinfunction "IRQ/GPIO8_1") (pintype "bidirectional"))
      (node (ref "XA1") (pin "P35") (pinfunction "P35-AP4_GP27/TT_DW_IRQ_P35") (pintype "bidirectional"))
    )
    (net (code "25") (name "DW_SPI_CIPO") (class "Default")
      (node (ref "U2") (pin "36") (pinfunction "SPICDO(MISO)_36") (pintype "bidirectional"))
      (node (ref "XA1") (pin "P10") (pinfunction "P10-AP4_GP33/TT_DW_SPI_IO1_P10") (pintype "bidirectional"))
    )
    (net (code "26") (name "DW_SPI_CLK") (class "Default")
      (node (ref "U2") (pin "34") (pinfunction "SPICLK_34") (pintype "bidirectional"))
      (node (ref "XA1") (pin "P12") (pinfunction "P12-AP4_GP31/TT_DW_SPI_CLK_P12") (pintype "bidirectional"))
    )
    (net (code "27") (name "DW_SPI_COPI") (class "Default")
      (node (ref "U2") (pin "35") (pinfunction "SPICDI(MOSI)_35") (pintype "bidirectional"))
      (node (ref "XA1") (pin "P11") (pinfunction "P11-AP4_GP32/TT_DW_SPI_IO0_P11") (pintype "bidirectional"))
    )
    (net (code "28") (name "DW_SYNC") (class "Default")
      (node (ref "TP7") (pin "P$1") (pinfunction "TESTPOINT_P$1") (pintype "bidirectional"))
      (node (ref "U2") (pin "9") (pinfunction "GPIO7/SYNC_9") (pintype "bidirectional"))
    )
    (net (code "29") (name "DW_VDD2_SUP") (class "Default")
      (node (ref "C13") (pin "1") (pinfunction "1_1") (pintype "bidirectional"))
      (node (ref "C24") (pin "1") (pinfunction "1_1") (pintype "bidirectional"))
      (node (ref "C55") (pin "1") (pinfunction "1_1") (pintype "bidirectional"))
      (node (ref "FB1") (pin "P$1") (pinfunction "P$1_P$1") (pintype "bidirectional"))
      (node (ref "RZ1") (pin "2") (pinfunction "2_2") (pintype "passive"))
      (node (ref "RZ4") (pin "2") (pinfunction "2_2") (pintype "passive"))
      (node (ref "U2") (pin "23") (pinfunction "VDD2B_23") (pintype "bidirectional"))
    )
    (net (code "30") (name "DW_VDD3_SUP") (class "Default")
      (node (ref "C14") (pin "1") (pinfunction "1_1") (pintype "bidirectional"))
      (node (ref "C22") (pin "1") (pinfunction "1_1") (pintype "bidirectional"))
      (node (ref "C54") (pin "1") (pinfunction "1_1") (pintype "bidirectional"))
      (node (ref "RX4") (pin "1") (pinfunction "1_1") (pintype "passive"))
      (node (ref "RZ2") (pin "2") (pinfunction "2_2") (pintype "passive"))
      (node (ref "U2") (pin "26") (pinfunction "VDD3_26") (pintype "bidirectional"))
    )
    (net (code "31") (name "DW_WAKEUP") (class "Default")
      (node (ref "U2") (pin "32") (pinfunction "WAKEUP_32") (pintype "bidirectional"))
      (node (ref "XA1") (pin "P34") (pinfunction "P34-AP4_GP26/TT_DW_WAKEUP_P34") (pintype "bidirectional"))
    )
    (net (code "32") (name "FLASH_CLK") (class "Default")
      (node (ref "U5") (pin "6") (pinfunction "CLK_6") (pintype "input"))
      (node (ref "XA1") (pin "P7") (pinfunction "P7-AP4_GP47/TT_FLASH_SCK_P7") (pintype "bidirectional"))
    )
    (net (code "33") (name "FLASH_PDI-IO0") (class "Default")
      (node (ref "U5") (pin "5") (pinfunction "DI_5") (pintype "bidirectional"))
      (node (ref "XA1") (pin "P6") (pinfunction "P6-AP4_GP48/TT_FLASH_MOSI_P6") (pintype "bidirectional"))
    )
    (net (code "34") (name "FLASH_PDO-IO1") (class "Default")
      (node (ref "U5") (pin "2") (pinfunction "DO_2") (pintype "bidirectional"))
      (node (ref "XA1") (pin "P5") (pinfunction "P5-AP4_GP49/TT_FLASH_MISO_P5") (pintype "bidirectional"))
    )
    (net (code "35") (name "FLASH_~{CS}") (class "Default")
      (node (ref "R21") (pin "1") (pinfunction "1_1") (pintype "passive"))
      (node (ref "U5") (pin "1") (pinfunction "~{CS}_1") (pintype "input"))
      (node (ref "XA1") (pin "P42") (pinfunction "P42-AP4_GP69/TT_FLASH_~{CS}_P42") (pintype "bidirectional"))
    )
    (net (code "36") (name "FLASH_~{HOLD}-IO3") (class "Default")
      (node (ref "U5") (pin "7") (pinfunction "~{HOLD}_7") (pintype "bidirectional"))
      (node (ref "XA1") (pin "P24") (pinfunction "P24-AP4_GP06/TT_FLASH_~{HOLD}_P24") (pintype "bidirectional"))
    )
    (net (code "37") (name "FLASH_~{WP}-IO2") (class "Default")
      (node (ref "U5") (pin "3") (pinfunction "~{WP}_3") (pintype "bidirectional"))
      (node (ref "XA1") (pin "P23") (pinfunction "P23-AP4_GP30/TT_FLASH_~{WP}_P23") (pintype "bidirectional"))
    )
    (net (code "38") (name "GND") (class "Default")
      (node (ref "C12") (pin "2") (pinfunction "2_2") (pintype "bidirectional"))
      (node (ref "C13") (pin "2") (pinfunction "2_2") (pintype "bidirectional"))
      (node (ref "C14") (pin "2") (pinfunction "2_2") (pintype "bidirectional"))
      (node (ref "C22") (pin "2") (pinfunction "2_2") (pintype "bidirectional"))
      (node (ref "C23") (pin "2") (pinfunction "2_2") (pintype "bidirectional"))
      (node (ref "C24") (pin "2") (pinfunction "2_2") (pintype "bidirectional"))
      (node (ref "C25") (pin "2") (pinfunction "2_2") (pintype "bidirectional"))
      (node (ref "C26") (pin "2") (pinfunction "2_2") (pintype "bidirectional"))
      (node (ref "C27") (pin "2") (pinfunction "2_2") (pintype "bidirectional"))
      (node (ref "C28") (pin "2") (pinfunction "2_2") (pintype "bidirectional"))
      (node (ref "C29") (pin "2") (pinfunction "2_2") (pintype "bidirectional"))
      (node (ref "C3") (pin "2") (pinfunction "2_2") (pintype "bidirectional"))
      (node (ref "C30") (pin "2") (pinfunction "2_2") (pintype "bidirectional"))
      (node (ref "C31") (pin "2") (pinfunction "2_2") (pintype "bidirectional"))
      (node (ref "C32") (pin "2") (pinfunction "2_2") (pintype "bidirectional"))
      (node (ref "C33") (pin "2") (pinfunction "2_2") (pintype "bidirectional"))
      (node (ref "C34") (pin "2") (pinfunction "2_2") (pintype "bidirectional"))
      (node (ref "C35") (pin "2") (pinfunction "2_2") (pintype "bidirectional"))
      (node (ref "C36") (pin "2") (pinfunction "2_2") (pintype "bidirectional"))
      (node (ref "C37") (pin "2") (pinfunction "2_2") (pintype "bidirectional"))
      (node (ref "C40") (pin "1") (pinfunction "1_1") (pintype "bidirectional"))
      (node (ref "C41") (pin "2") (pinfunction "2_2") (pintype "bidirectional"))
      (node (ref "C42") (pin "2") (pinfunction "2_2") (pintype "bidirectional"))
      (node (ref "C43") (pin "2") (pinfunction "2_2") (pintype "bidirectional"))
      (node (ref "C44") (pin "2") (pinfunction "2_2") (pintype "bidirectional"))
      (node (ref "C45") (pin "1") (pinfunction "1_1") (pintype "bidirectional"))
      (node (ref "C46") (pin "2") (pinfunction "2_2") (pintype "bidirectional"))
      (node (ref "C47") (pin "1") (pinfunction "1_1") (pintype "bidirectional"))
      (node (ref "C48") (pin "2") (pinfunction "2_2") (pintype "bidirectional"))
      (node (ref "C49") (pin "2") (pinfunction "2_2") (pintype "bidirectional"))
      (node (ref "C5") (pin "P$1") (pinfunction "1_P$1") (pintype "bidirectional"))
      (node (ref "C50") (pin "1") (pinfunction "1_1") (pintype "bidirectional"))
      (node (ref "C51") (pin "1") (pinfunction "1_1") (pintype "bidirectional"))
      (node (ref "C52") (pin "1") (pinfunction "1_1") (pintype "bidirectional"))
      (node (ref "C53") (pin "2") (pinfunction "2_2") (pintype "bidirectional"))
      (node (ref "C54") (pin "2") (pinfunction "2_2") (pintype "bidirectional"))
      (node (ref "C55") (pin "2") (pinfunction "2_2") (pintype "bidirectional"))
      (node (ref "C56") (pin "2") (pinfunction "2_2") (pintype "bidirectional"))
      (node (ref "C57") (pin "2") (pinfunction "2_2") (pintype "bidirectional"))
      (node (ref "C6") (pin "P$1") (pinfunction "1_P$1") (pintype "bidirectional"))
      (node (ref "CX1") (pin "2") (pinfunction "2_2") (pintype "bidirectional"))
      (node (ref "CX2") (pin "2") (pinfunction "2_2") (pintype "bidirectional"))
      (node (ref "J1") (pin "5") (pinfunction "GND_5") (pintype "bidirectional"))
      (node (ref "J4") (pin "1") (pinfunction "1_1") (pintype "bidirectional"))
      (node (ref "J4") (pin "1SUPP") (pinfunction "1_1SUPP") (pintype "bidirectional"))
      (node (ref "JP6") (pin "1") (pinfunction "1_1") (pintype "passive"))
      (node (ref "JP9") (pin "2") (pinfunction "2_2") (pintype "passive"))
      (node (ref "Q2") (pin "S") (pinfunction "S_S") (pintype "passive"))
      (node (ref "R1") (pin "2") (pinfunction "2_2") (pintype "passive"))
      (node (ref "R10") (pin "1") (pinfunction "1_1") (pintype "passive"))
      (node (ref "R14") (pin "1") (pinfunction "1_1") (pintype "passive"))
      (node (ref "R15") (pin "1") (pinfunction "1_1") (pintype "passive"))
      (node (ref "R24") (pin "1") (pinfunction "1_1") (pintype "passive"))
      (node (ref "R25") (pin "2") (pinfunction "2_2") (pintype "passive"))
      (node (ref "R26") (pin "1") (pinfunction "1_1") (pintype "passive"))
      (node (ref "R27") (pin "1") (pinfunction "1_1") (pintype "passive"))
      (node (ref "R30") (pin "1") (pinfunction "1_1") (pintype "passive"))
      (node (ref "R6") (pin "2") (pinfunction "2_2") (pintype "passive"))
      (node (ref "RX7") (pin "1") (pinfunction "1_1") (pintype "passive"))
      (node (ref "S2") (pin "10") (pinfunction "GND_10") (pintype "bidirectional"))
      (node (ref "S2") (pin "12") (pinfunction "GND_12") (pintype "bidirectional"))
      (node (ref "S2") (pin "2") (pinfunction "GND_2") (pintype "bidirectional"))
      (node (ref "S2") (pin "7") (pinfunction "GND_7") (pintype "bidirectional"))
      (node (ref "S2") (pin "8") (pinfunction "GND_8") (pintype "bidirectional"))
      (node (ref "S2") (pin "PAD") (pinfunction "GND_PAD") (pintype "bidirectional"))
      (node (ref "S3") (pin "6") (pinfunction "GND_6") (pintype "bidirectional"))
      (node (ref "S3") (pin "7") (pinfunction "GND_7") (pintype "bidirectional"))
      (node (ref "S3") (pin "PAD") (pinfunction "GND_PAD") (pintype "bidirectional"))
      (node (ref "S4") (pin "G1") (pinfunction "GND_G1") (pintype "bidirectional"))
      (node (ref "S4") (pin "G2") (pinfunction "GND_G2") (pintype "bidirectional"))
      (node (ref "U2") (pin "10") (pinfunction "GND-RF_10") (pintype "bidirectional"))
      (node (ref "U2") (pin "11") (pinfunction "GND-RF_11") (pintype "bidirectional"))
      (node (ref "U2") (pin "12") (pinfunction "GND-RF_12") (pintype "bidirectional"))
      (node (ref "U2") (pin "14") (pinfunction "GND-RF_14") (pintype "bidirectional"))
      (node (ref "U2") (pin "15") (pinfunction "GND-RF_15") (pintype "bidirectional"))
      (node (ref "U2") (pin "16") (pinfunction "GND-RF_16") (pintype "bidirectional"))
      (node (ref "U2") (pin "17") (pinfunction "GND-RF_17") (pintype "bidirectional"))
      (node (ref "U2") (pin "19") (pinfunction "GND-RF_19") (pintype "bidirectional"))
      (node (ref "U2") (pin "20") (pinfunction "GND-RF_20") (pintype "bidirectional"))
      (node (ref "U2") (pin "24") (pinfunction "VSS2_24") (pintype "bidirectional"))
      (node (ref "U2") (pin "25") (pinfunction "VSS3_25") (pintype "bidirectional"))
      (node (ref "U2") (pin "30") (pinfunction "VSS1_30") (pintype "bidirectional"))
      (node (ref "U2") (pin "39") (pinfunction "VSS_39") (pintype "bidirectional"))
      (node (ref "U2") (pin "40") (pinfunction "VSS_40") (pintype "bidirectional"))
      (node (ref "U3") (pin "3") (pinfunction "VSS_3") (pintype "bidirectional"))
      (node (ref "U3") (pin "7") (pinfunction "ISET2_7") (pintype "bidirectional"))
      (node (ref "U3") (pin "PAD") (pinfunction "VSS_PAD") (pintype "bidirectional"))
      (node (ref "U4") (pin "1") (pinfunction "PGND_1") (pintype "bidirectional"))
      (node (ref "U4") (pin "10") (pinfunction "EN1_10") (pintype "bidirectional"))
      (node (ref "U4") (pin "11") (pinfunction "EN2_11") (pintype "bidirectional"))
      (node (ref "U4") (pin "20") (pinfunction "PGND_20") (pintype "bidirectional"))
      (node (ref "U4") (pin "PAD") (pinfunction "PGND_PAD") (pintype "bidirectional"))
      (node (ref "U5") (pin "4") (pinfunction "GND_4") (pintype "bidirectional"))
      (node (ref "U6") (pin "18") (pinfunction "COM2_18") (pintype "bidirectional"))
      (node (ref "U6") (pin "2") (pinfunction "GND_2") (pintype "bidirectional"))
      (node (ref "U6") (pin "25") (pinfunction "GNDIO_25") (pintype "bidirectional"))
      (node (ref "U6") (pin "5") (pinfunction "PS1_5") (pintype "input"))
      (node (ref "U6") (pin "6") (pinfunction "PS0_6") (pintype "input"))
      (node (ref "VR1") (pin "13") (pinfunction "GND2_13") (pintype "bidirectional"))
      (node (ref "VR1") (pin "3") (pinfunction "GND2_3") (pintype "bidirectional"))
      (node (ref "VR1") (pin "9") (pinfunction "GND1_9") (pintype "bidirectional"))
      (node (ref "VR3") (pin "2") (pinfunction "GND_2") (pintype "bidirectional"))
      (node (ref "VR3") (pin "PAD") (pinfunction "GND_PAD") (pintype "bidirectional"))
      (node (ref "XA1") (pin "P13") (pinfunction "P13-GND_P13") (pintype "bidirectional"))
      (node (ref "XA1") (pin "P37") (pinfunction "P37-GND_P37") (pintype "bidirectional"))
      (node (ref "XJ1") (pin "A1/B12") (pinfunction "GND_A1/B12") (pintype "power_in"))
      (node (ref "XJ1") (pin "B1/A12") (pinfunction "GND_B1/A12") (pintype "power_in"))
      (node (ref "XJ1") (pin "S1") (pinfunction "GND_S1") (pintype "power_in"))
      (node (ref "XJ1") (pin "S2") (pinfunction "GND_S2") (pintype "power_in"))
      (node (ref "XJ1") (pin "S3") (pinfunction "GND_S3") (pintype "power_in"))
      (node (ref "XJ1") (pin "S4") (pinfunction "GND_S4") (pintype "power_in"))
      (node (ref "XR16") (pin "2") (pinfunction "2_2") (pintype "passive"))
      (node (ref "XR17") (pin "2") (pinfunction "2_2") (pintype "passive"))
      (node (ref "XR19") (pin "1") (pinfunction "1_1") (pintype "passive"))
      (node (ref "Y1") (pin "1") (pinfunction "GND_1") (pintype "bidirectional"))
      (node (ref "Y1") (pin "2") (pinfunction "GND_2") (pintype "bidirectional"))
    )
    (net (code "39") (name "Net-(A4-ANTENNA)") (class "Default")
      (node (ref "A4") (pin "S1") (pinfunction "ANTENNA_S1") (pintype "bidirectional"))
      (node (ref "C1") (pin "1") (pinfunction "1_1") (pintype "bidirectional"))
      (node (ref "L3") (pin "1") (pinfunction "1_1") (pintype "bidirectional"))
    )
    (net (code "40") (name "Net-(C4-1)") (class "Default")
      (node (ref "C4") (pin "P$1") (pinfunction "1_P$1") (pintype "bidirectional"))
      (node (ref "U2") (pin "18") (pinfunction "RF1_18") (pintype "bidirectional"))
    )
    (net (code "41") (name "Net-(C4-2)") (class "Default")
      (node (ref "C4") (pin "P$2") (pinfunction "2_P$2") (pintype "bidirectional"))
      (node (ref "S2") (pin "11") (pinfunction "RFC_11") (pintype "bidirectional"))
    )
    (net (code "42") (name "Net-(C5-2)") (class "Default")
      (node (ref "C5") (pin "P$2") (pinfunction "2_P$2") (pintype "bidirectional"))
      (node (ref "U6") (pin "27") (pinfunction "XIN32_27") (pintype "bidirectional"))
      (node (ref "X2") (pin "2") (pinfunction "2_2") (pintype "bidirectional"))
    )
    (net (code "43") (name "Net-(C6-2)") (class "Default")
      (node (ref "C6") (pin "P$2") (pinfunction "2_P$2") (pintype "bidirectional"))
      (node (ref "U6") (pin "26") (pinfunction "XOUT32_26") (pintype "bidirectional"))
      (node (ref "X2") (pin "1") (pinfunction "1_1") (pintype "bidirectional"))
    )
    (net (code "44") (name "Net-(C7-2)") (class "Default")
      (node (ref "C7") (pin "P$2") (pinfunction "2_P$2") (pintype "bidirectional"))
      (node (ref "R26") (pin "2") (pinfunction "2_2") (pintype "passive"))
      (node (ref "R28") (pin "1") (pinfunction "1_1") (pintype "passive"))
      (node (ref "VR1") (pin "10") (pinfunction "FB2_10") (pintype "bidirectional"))
    )
    (net (code "45") (name "Net-(C8-1)") (class "Default")
      (node (ref "C8") (pin "P$1") (pinfunction "1_P$1") (pintype "bidirectional"))
      (node (ref "R27") (pin "2") (pinfunction "2_2") (pintype "passive"))
      (node (ref "R29") (pin "2") (pinfunction "2_2") (pintype "passive"))
      (node (ref "VR1") (pin "4") (pinfunction "FB1_4") (pintype "bidirectional"))
    )
    (net (code "46") (name "Net-(D1-PadA1)") (class "Default")
      (node (ref "D1") (pin "A1") (pinfunction "A1_A1") (pintype "bidirectional"))
      (node (ref "D1") (pin "A2") (pinfunction "A2_A2") (pintype "bidirectional"))
      (node (ref "D2") (pin "A1") (pinfunction "A1_A1") (pintype "bidirectional"))
      (node (ref "D2") (pin "A2") (pinfunction "A2_A2") (pintype "bidirectional"))
      (node (ref "JP1") (pin "1") (pinfunction "1_1") (pintype "passive"))
    )
    (net (code "47") (name "Net-(D1-PadC1)") (class "Default")
      (node (ref "D1") (pin "C1") (pinfunction "C1_C1") (pintype "bidirectional"))
      (node (ref "R5") (pin "1") (pinfunction "1_1") (pintype "passive"))
    )
    (net (code "48") (name "Net-(D1-PadC2)") (class "Default")
      (node (ref "D1") (pin "C2") (pinfunction "C2_C2") (pintype "bidirectional"))
      (node (ref "R2") (pin "1") (pinfunction "1_1") (pintype "passive"))
    )
    (net (code "49") (name "Net-(D2-PadC1)") (class "Default")
      (node (ref "D2") (pin "C1") (pinfunction "C1_C1") (pintype "bidirectional"))
      (node (ref "R4") (pin "1") (pinfunction "1_1") (pintype "passive"))
    )
    (net (code "50") (name "Net-(D2-PadC2)") (class "Default")
      (node (ref "D2") (pin "C2") (pinfunction "C2_C2") (pintype "bidirectional"))
      (node (ref "R3") (pin "1") (pinfunction "1_1") (pintype "passive"))
    )
    (net (code "51") (name "Net-(JP2-Pad1)") (class "Default")
      (node (ref "JP2") (pin "1") (pinfunction "1_1") (pintype "passive"))
      (node (ref "XR19") (pin "2") (pinfunction "2_2") (pintype "passive"))
    )
    (net (code "52") (name "Net-(L1-1)") (class "Default")
      (node (ref "L1") (pin "P$1") (pinfunction "1_P$1") (pintype "bidirectional"))
      (node (ref "VR1") (pin "2") (pinfunction "LX2_2") (pintype "bidirectional"))
    )
    (net (code "53") (name "Net-(L2-2)") (class "Default")
      (node (ref "L2") (pin "P$2") (pinfunction "2_P$2") (pintype "bidirectional"))
      (node (ref "VR1") (pin "8") (pinfunction "LX1_8") (pintype "bidirectional"))
    )
    (net (code "54") (name "Net-(L4-1)") (class "Default")
      (node (ref "C17") (pin "2") (pinfunction "2_2") (pintype "bidirectional"))
      (node (ref "C18") (pin "2") (pinfunction "2_2") (pintype "bidirectional"))
      (node (ref "C19") (pin "2") (pinfunction "2_2") (pintype "bidirectional"))
      (node (ref "L4") (pin "P$1") (pinfunction "1_P$1") (pintype "bidirectional"))
    )
    (net (code "55") (name "Net-(L4-2)") (class "Default")
      (node (ref "C10") (pin "2") (pinfunction "2_2") (pintype "bidirectional"))
      (node (ref "C16") (pin "2") (pinfunction "2_2") (pintype "bidirectional"))
      (node (ref "C21") (pin "2") (pinfunction "2_2") (pintype "bidirectional"))
      (node (ref "C39") (pin "2") (pinfunction "2_2") (pintype "bidirectional"))
      (node (ref "C9") (pin "2") (pinfunction "2_2") (pintype "bidirectional"))
      (node (ref "L4") (pin "P$2") (pinfunction "2_P$2") (pintype "bidirectional"))
      (node (ref "U4") (pin "19") (pinfunction "AC2_19") (pintype "bidirectional"))
    )
    (net (code "56") (name "Net-(LS1-N)") (class "Default")
      (node (ref "D4") (pin "ANODE") (pinfunction "ANODE_ANODE") (pintype "bidirectional"))
      (node (ref "LS1") (pin "-") (pinfunction "N_-") (pintype "passive"))
      (node (ref "Q2") (pin "D") (pinfunction "D_D") (pintype "passive"))
    )
    (net (code "57") (name "Net-(LS1-P)") (class "Default")
      (node (ref "C44") (pin "1") (pinfunction "1_1") (pintype "bidirectional"))
      (node (ref "D4") (pin "CATHODE") (pinfunction "CATHODE_CATHODE") (pintype "bidirectional"))
      (node (ref "JP8") (pin "2") (pinfunction "2_2") (pintype "passive"))
      (node (ref "LS1") (pin "+") (pinfunction "P_+") (pintype "passive"))
    )
    (net (code "58") (name "Net-(R6-Pad1)") (class "Default")
      (node (ref "R6") (pin "1") (pinfunction "1_1") (pintype "passive"))
      (node (ref "R7") (pin "2") (pinfunction "2_2") (pintype "passive"))
    )
    (net (code "59") (name "Net-(R8-Pad2)") (class "Default")
      (node (ref "R8") (pin "2") (pinfunction "2_2") (pintype "passive"))
      (node (ref "R9") (pin "1") (pinfunction "1_1") (pintype "passive"))
    )
    (net (code "60") (name "Net-(R11-Pad2)") (class "Default")
      (node (ref "R11") (pin "2") (pinfunction "2_2") (pintype "passive"))
      (node (ref "RX2") (pin "1") (pinfunction "1_1") (pintype "passive"))
      (node (ref "RX3") (pin "1") (pinfunction "1_1") (pintype "passive"))
      (node (ref "RZ4") (pin "1") (pinfunction "1_1") (pintype "passive"))
    )
    (net (code "61") (name "Net-(R13-Pad1)") (class "Default")
      (node (ref "R13") (pin "1") (pinfunction "1_1") (pintype "passive"))
      (node (ref "R14") (pin "2") (pinfunction "2_2") (pintype "passive"))
    )
    (net (code "62") (name "Net-(R13-Pad2)") (class "Default")
      (node (ref "R13") (pin "2") (pinfunction "2_2") (pintype "passive"))
      (node (ref "RT1") (pin "1") (pinfunction "1_1") (pintype "passive"))
    )
    (net (code "63") (name "Net-(R18-Pad2)") (class "Default")
      (node (ref "R18") (pin "2") (pinfunction "2_2") (pintype "passive"))
      (node (ref "R23") (pin "1") (pinfunction "1_1") (pintype "passive"))
    )
    (net (code "64") (name "Net-(S3A-OUT)") (class "Default")
      (node (ref "C33") (pin "1") (pinfunction "1_1") (pintype "bidirectional"))
      (node (ref "RZ1") (pin "1") (pinfunction "1_1") (pintype "passive"))
      (node (ref "S3") (pin "8") (pinfunction "OUT_8") (pintype "bidirectional"))
    )
    (net (code "65") (name "Net-(S3B-OUT)") (class "Default")
      (node (ref "C25") (pin "1") (pinfunction "1_1") (pintype "bidirectional"))
      (node (ref "RZ2") (pin "1") (pinfunction "1_1") (pintype "passive"))
      (node (ref "S3") (pin "5") (pinfunction "OUT_5") (pintype "bidirectional"))
    )
    (net (code "66") (name "Net-(TP0-TESTPOINT)") (class "Default")
      (node (ref "TP0") (pin "P$1") (pinfunction "TESTPOINT_P$1") (pintype "bidirectional"))
      (node (ref "U2") (pin "3") (pinfunction "GPIO0/RXOKLED_3") (pintype "bidirectional"))
    )
    (net (code "67") (name "Net-(TP1-TESTPOINT)") (class "Default")
      (node (ref "TP1") (pin "P$1") (pinfunction "TESTPOINT_P$1") (pintype "bidirectional"))
      (node (ref "U2") (pin "4") (pinfunction "GPIO1/SFDLED_4") (pintype "bidirectional"))
    )
    (net (code "68") (name "Net-(TP2-TESTPOINT)") (class "Default")
      (node (ref "TP2") (pin "P$1") (pinfunction "TESTPOINT_P$1") (pintype "bidirectional"))
      (node (ref "U2") (pin "6") (pinfunction "GPIO2/RXLED_6") (pintype "bidirectional"))
    )
    (net (code "69") (name "Net-(TP3-TESTPOINT)") (class "Default")
      (node (ref "TP3") (pin "P$1") (pinfunction "TESTPOINT_P$1") (pintype "bidirectional"))
      (node (ref "U2") (pin "7") (pinfunction "GPIO3/TXLED_7") (pintype "bidirectional"))
    )
    (net (code "70") (name "Net-(TP4-TESTPOINT)") (class "Default")
      (node (ref "TP4") (pin "P$1") (pinfunction "TESTPOINT_P$1") (pintype "bidirectional"))
      (node (ref "U2") (pin "8") (pinfunction "GPIO4/EXTPA_8") (pintype "bidirectional"))
    )
    (net (code "71") (name "Net-(TP5-TESTPOINT)") (class "Default")
      (node (ref "TP5") (pin "P$1") (pinfunction "TESTPOINT_P$1") (pintype "bidirectional"))
      (node (ref "U2") (pin "5") (pinfunction "GPIO5/EXTTXE/SPIPOL_5") (pintype "bidirectional"))
    )
    (net (code "72") (name "Net-(TP6-TESTPOINT)") (class "Default")
      (node (ref "TP6") (pin "P$1") (pinfunction "TESTPOINT_P$1") (pintype "bidirectional"))
      (node (ref "U2") (pin "2") (pinfunction "GPIO6/EXTRXE/SPIPHA_2") (pintype "bidirectional"))
    )
    (net (code "73") (name "Net-(U2-RF2)") (class "Default")
      (node (ref "R1") (pin "1") (pinfunction "1_1") (pintype "passive"))
      (node (ref "U2") (pin "13") (pinfunction "RF2_13") (pintype "bidirectional"))
    )
    (net (code "74") (name "Net-(U2-VDD2A)") (class "Default")
      (node (ref "C12") (pin "1") (pinfunction "1_1") (pintype "bidirectional"))
      (node (ref "FB1") (pin "P$2") (pinfunction "P$2_P$2") (pintype "bidirectional"))
      (node (ref "U2") (pin "28") (pinfunction "VDD2A_28") (pintype "bidirectional"))
    )
    (net (code "75") (name "Net-(U2-VIO_D)") (class "Default")
      (node (ref "C23") (pin "1") (pinfunction "1_1") (pintype "bidirectional"))
      (node (ref "U2") (pin "38") (pinfunction "VIO_D_38") (pintype "bidirectional"))
    )
    (net (code "76") (name "Net-(U2-VTX_D)") (class "Default")
      (node (ref "C36") (pin "1") (pinfunction "1_1") (pintype "bidirectional"))
      (node (ref "U2") (pin "27") (pinfunction "VTX_D_27") (pintype "bidirectional"))
    )
    (net (code "77") (name "Net-(U2-XTO)") (class "Default")
      (node (ref "C3") (pin "1") (pinfunction "1_1") (pintype "bidirectional"))
      (node (ref "U2") (pin "22") (pinfunction "XTO_22") (pintype "bidirectional"))
    )
    (net (code "78") (name "Net-(U3-ISET)") (class "Default")
      (node (ref "R15") (pin "2") (pinfunction "2_2") (pintype "passive"))
      (node (ref "U3") (pin "2") (pinfunction "ISET_2") (pintype "bidirectional"))
    )
    (net (code "79") (name "Net-(U3-PRETERM)") (class "Default")
      (node (ref "RX7") (pin "2") (pinfunction "2_2") (pintype "passive"))
      (node (ref "U3") (pin "4") (pinfunction "PRETERM_4") (pintype "bidirectional"))
    )
    (net (code "80") (name "Net-(U4-AC1)") (class "Default")
      (node (ref "C10") (pin "1") (pinfunction "1_1") (pintype "bidirectional"))
      (node (ref "C15") (pin "2") (pinfunction "2_2") (pintype "bidirectional"))
      (node (ref "C17") (pin "1") (pinfunction "1_1") (pintype "bidirectional"))
      (node (ref "C18") (pin "1") (pinfunction "1_1") (pintype "bidirectional"))
      (node (ref "C19") (pin "1") (pinfunction "1_1") (pintype "bidirectional"))
      (node (ref "C20") (pin "2") (pinfunction "2_2") (pintype "bidirectional"))
      (node (ref "C38") (pin "2") (pinfunction "2_2") (pintype "bidirectional"))
      (node (ref "C9") (pin "1") (pinfunction "1_1") (pintype "bidirectional"))
      (node (ref "U4") (pin "2") (pinfunction "AC1_2") (pintype "bidirectional"))
    )
    (net (code "81") (name "Net-(U4-BOOT1)") (class "Default")
      (node (ref "C15") (pin "1") (pinfunction "1_1") (pintype "bidirectional"))
      (node (ref "U4") (pin "3") (pinfunction "BOOT1_3") (pintype "bidirectional"))
    )
    (net (code "82") (name "Net-(U4-BOOT2)") (class "Default")
      (node (ref "C16") (pin "1") (pinfunction "1_1") (pintype "bidirectional"))
      (node (ref "U4") (pin "17") (pinfunction "BOOT2_17") (pintype "bidirectional"))
    )
    (net (code "83") (name "Net-(U4-CLAMP1)") (class "Default")
      (node (ref "C38") (pin "1") (pinfunction "1_1") (pintype "bidirectional"))
      (node (ref "U4") (pin "5") (pinfunction "CLAMP1_5") (pintype "bidirectional"))
    )
    (net (code "84") (name "Net-(U4-CLAMP2)") (class "Default")
      (node (ref "C39") (pin "1") (pinfunction "1_1") (pintype "bidirectional"))
      (node (ref "U4") (pin "16") (pinfunction "CLAMP2_16") (pintype "bidirectional"))
    )
    (net (code "85") (name "Net-(U4-COMM1)") (class "Default")
      (node (ref "C20") (pin "1") (pinfunction "1_1") (pintype "bidirectional"))
      (node (ref "U4") (pin "6") (pinfunction "COMM1_6") (pintype "bidirectional"))
    )
    (net (code "86") (name "Net-(U4-COMM2)") (class "Default")
      (node (ref "C21") (pin "1") (pinfunction "1_1") (pintype "bidirectional"))
      (node (ref "U4") (pin "15") (pinfunction "COMM2_15") (pintype "bidirectional"))
    )
    (net (code "87") (name "Net-(U4-FOD)") (class "Default")
      (node (ref "R23") (pin "2") (pinfunction "2_2") (pintype "passive"))
      (node (ref "R7") (pin "1") (pinfunction "1_1") (pintype "passive"))
      (node (ref "R9") (pin "2") (pinfunction "2_2") (pintype "passive"))
      (node (ref "U4") (pin "14") (pinfunction "FOD_14") (pintype "bidirectional"))
    )
    (net (code "88") (name "Net-(U4-ILIM)") (class "Default")
      (node (ref "R8") (pin "1") (pinfunction "1_1") (pintype "passive"))
      (node (ref "U4") (pin "12") (pinfunction "ILIM_12") (pintype "bidirectional"))
    )
    (net (code "89") (name "Net-(U4-RECT)") (class "Default")
      (node (ref "C28") (pin "1") (pinfunction "1_1") (pintype "bidirectional"))
      (node (ref "C56") (pin "1") (pinfunction "1_1") (pintype "bidirectional"))
      (node (ref "C57") (pin "1") (pinfunction "1_1") (pintype "bidirectional"))
      (node (ref "R18") (pin "1") (pinfunction "1_1") (pintype "passive"))
      (node (ref "U4") (pin "18") (pinfunction "RECT_18") (pintype "bidirectional"))
    )
    (net (code "90") (name "Net-(U6-CAP)") (class "Default")
      (node (ref "C43") (pin "1") (pinfunction "1_1") (pintype "bidirectional"))
      (node (ref "U6") (pin "9") (pinfunction "CAP_9") (pintype "bidirectional"))
    )
    (net (code "91") (name "Net-(U6-COM3)") (class "Default")
      (node (ref "JP6") (pin "2") (pinfunction "2_2") (pintype "passive"))
      (node (ref "U6") (pin "17") (pinfunction "COM3_17") (pintype "bidirectional"))
    )
    (net (code "92") (name "Net-(VR3-EN)") (class "Default")
      (node (ref "RX1") (pin "2") (pinfunction "2_2") (pintype "passive"))
      (node (ref "RZ3") (pin "2") (pinfunction "2_2") (pintype "passive"))
      (node (ref "VR3") (pin "3") (pinfunction "EN_3") (pintype "input"))
    )
    (net (code "93") (name "Net-(VR3-OUT)") (class "Default")
      (node (ref "C52") (pin "2") (pinfunction "2_2") (pintype "bidirectional"))
      (node (ref "RZ5") (pin "1") (pinfunction "1_1") (pintype "passive"))
      (node (ref "VR3") (pin "1") (pinfunction "OUT_1") (pintype "power_in"))
    )
    (net (code "94") (name "Net-(XA1-P15-BLE_RFOUT)") (class "Default")
      (node (ref "C2") (pin "1") (pinfunction "1_1") (pintype "bidirectional"))
      (node (ref "L3") (pin "2") (pinfunction "2_2") (pintype "bidirectional"))
      (node (ref "XA1") (pin "P15") (pinfunction "P15-BLE_RFOUT_P15") (pintype "bidirectional"))
    )
    (net (code "95") (name "Net-(XJ1-CC1)") (class "Default")
      (node (ref "XJ1") (pin "A5") (pinfunction "CC1_A5") (pintype "bidirectional"))
      (node (ref "XR16") (pin "1") (pinfunction "1_1") (pintype "passive"))
    )
    (net (code "96") (name "Net-(XJ1-CC2)") (class "Default")
      (node (ref "XJ1") (pin "B5") (pinfunction "CC2_B5") (pintype "bidirectional"))
      (node (ref "XR17") (pin "1") (pinfunction "1_1") (pintype "passive"))
    )
    (net (code "97") (name "Net-(Y1-OSC)") (class "Default")
      (node (ref "C11") (pin "2") (pinfunction "2_2") (pintype "bidirectional"))
      (node (ref "Y1") (pin "3") (pinfunction "OSC_3") (pintype "bidirectional"))
    )
    (net (code "98") (name "QI_TS_CTRL") (class "Default")
      (node (ref "C30") (pin "1") (pinfunction "1_1") (pintype "bidirectional"))
      (node (ref "RT1") (pin "2") (pinfunction "2_2") (pintype "passive"))
      (node (ref "U4") (pin "13") (pinfunction "TS/CTRL_13") (pintype "bidirectional"))
      (node (ref "XA1") (pin "P44") (pinfunction "P44-AP4_GP66/TT_QI_TS_CTRL_P44") (pintype "bidirectional"))
    )
    (net (code "99") (name "RF1") (class "Default")
      (node (ref "A1") (pin "FEED") (pinfunction "ANTENNA_FEED") (pintype "bidirectional"))
      (node (ref "S2") (pin "9") (pinfunction "J2_9") (pintype "bidirectional"))
    )
    (net (code "100") (name "RF2") (class "Default")
      (node (ref "A2") (pin "FEED") (pinfunction "ANTENNA_FEED") (pintype "bidirectional"))
      (node (ref "S2") (pin "3") (pinfunction "J3_3") (pintype "bidirectional"))
    )
    (net (code "101") (name "RF3") (class "Default")
      (node (ref "A3") (pin "FEED") (pinfunction "ANTENNA_FEED") (pintype "bidirectional"))
      (node (ref "S2") (pin "1") (pinfunction "J1_1") (pintype "bidirectional"))
      (node (ref "S4") (pin "IN") (pinfunction "IN_IN") (pintype "bidirectional"))
      (node (ref "S4") (pin "OUT") (pinfunction "A_OUT") (pintype "bidirectional"))
    )
    (net (code "102") (name "RFSW_V1") (class "Default")
      (node (ref "CX2") (pin "1") (pinfunction "1_1") (pintype "bidirectional"))
      (node (ref "S2") (pin "4") (pinfunction "V1_4") (pintype "input"))
      (node (ref "XA1") (pin "P8") (pinfunction "P8-AP4_GP24/TT_RFSW_V1_P8") (pintype "bidirectional"))
    )
    (net (code "103") (name "RFSW_V2") (class "Default")
      (node (ref "CX1") (pin "1") (pinfunction "1_1") (pintype "bidirectional"))
      (node (ref "S2") (pin "5") (pinfunction "V2_5") (pintype "input"))
      (node (ref "XA1") (pin "P9") (pinfunction "P9-AP4_GP25/TT_RFSW_V2_P9") (pintype "bidirectional"))
    )
    (net (code "104") (name "TC_OSC_38P4MHZ") (class "Default")
      (node (ref "C11") (pin "1") (pinfunction "1_1") (pintype "bidirectional"))
      (node (ref "R10") (pin "2") (pinfunction "2_2") (pintype "passive"))
      (node (ref "R11") (pin "1") (pinfunction "1_1") (pintype "passive"))
      (node (ref "U2") (pin "21") (pinfunction "XTI_21") (pintype "bidirectional"))
    )
    (net (code "105") (name "VBAT") (class "Default")
      (node (ref "C42") (pin "1") (pinfunction "1_1") (pintype "bidirectional"))
      (node (ref "J4") (pin "3") (pinfunction "3_3") (pintype "bidirectional"))
      (node (ref "J4") (pin "3SUPP") (pinfunction "3_3SUPP") (pintype "bidirectional"))
      (node (ref "JP9") (pin "1") (pinfunction "1_1") (pintype "passive"))
      (node (ref "S1") (pin "2") (pinfunction "2_2") (pintype "passive"))
      (node (ref "U3") (pin "10") (pinfunction "OUT_10") (pintype "bidirectional"))
    )
    (net (code "106") (name "VBAT_SWITCHED") (class "Default")
      (node (ref "C45") (pin "2") (pinfunction "2_2") (pintype "bidirectional"))
      (node (ref "C48") (pin "1") (pinfunction "1_1") (pintype "bidirectional"))
      (node (ref "JP8") (pin "1") (pinfunction "1_1") (pintype "passive"))
      (node (ref "R31") (pin "2") (pinfunction "2_2") (pintype "passive"))
      (node (ref "R33") (pin "1") (pinfunction "1_1") (pintype "passive"))
      (node (ref "R34") (pin "1") (pinfunction "1_1") (pintype "passive"))
      (node (ref "S1") (pin "3") (pinfunction "3_3") (pintype "passive"))
      (node (ref "VR1") (pin "1") (pinfunction "VIN2_1") (pintype "bidirectional"))
      (node (ref "VR1") (pin "7") (pinfunction "VIN1_7") (pintype "bidirectional"))
    )
    (net (code "107") (name "VDD_TCXO") (class "Default")
      (node (ref "C26") (pin "1") (pinfunction "1_1") (pintype "bidirectional"))
      (node (ref "RX3") (pin "2") (pinfunction "2_2") (pintype "passive"))
      (node (ref "RX4") (pin "2") (pinfunction "2_2") (pintype "passive"))
      (node (ref "RZ5") (pin "2") (pinfunction "2_2") (pintype "passive"))
      (node (ref "Y1") (pin "4") (pinfunction "VDD_4") (pintype "bidirectional"))
    )
    (net (code "108") (name "VQI") (class "Default")
      (node (ref "C29") (pin "1") (pinfunction "1_1") (pintype "bidirectional"))
      (node (ref "C41") (pin "1") (pinfunction "1_1") (pintype "bidirectional"))
      (node (ref "C53") (pin "1") (pinfunction "1_1") (pintype "bidirectional"))
      (node (ref "Q1") (pin "A2") (pinfunction "D1_A2") (pintype "bidirectional"))
      (node (ref "Q1") (pin "A3") (pinfunction "D1_A3") (pintype "bidirectional"))
      (node (ref "Q1") (pin "B3") (pinfunction "D1_B3") (pintype "bidirectional"))
      (node (ref "U3") (pin "1") (pinfunction "IN_1") (pintype "bidirectional"))
      (node (ref "U4") (pin "4") (pinfunction "OUT_4") (pintype "bidirectional"))
    )
    (net (code "109") (name "VR1_1P8_EN") (class "Default")
      (node (ref "R34") (pin "2") (pinfunction "2_2") (pintype "passive"))
      (node (ref "VR1") (pin "6") (pinfunction "EN1_6") (pintype "bidirectional"))
    )
    (net (code "110") (name "VR1_2P5_EN") (class "Default")
      (node (ref "R33") (pin "2") (pinfunction "2_2") (pintype "passive"))
      (node (ref "VR1") (pin "12") (pinfunction "EN2_12") (pintype "bidirectional"))
    )
    (net (code "111") (name "VUSB") (class "Default")
      (node (ref "C40") (pin "2") (pinfunction "2_2") (pintype "bidirectional"))
      (node (ref "Q1") (pin "B2") (pinfunction "D2_B2") (pintype "bidirectional"))
      (node (ref "Q1") (pin "C2") (pinfunction "D2_C2") (pintype "bidirectional"))
      (node (ref "Q1") (pin "C3") (pinfunction "D2_C3") (pintype "bidirectional"))
      (node (ref "U4") (pin "9") (pinfunction "AD_9") (pintype "bidirectional"))
      (node (ref "XJ1") (pin "A4/B9") (pinfunction "VBUS_A4/B9") (pintype "power_in"))
      (node (ref "XJ1") (pin "B4/A9") (pinfunction "VBUS_B4/A9") (pintype "power_in"))
    )
    (net (code "112") (name "unconnected-(J1-SWO-Pad6)") (class "Default")
      (node (ref "J1") (pin "6") (pinfunction "SWO_6") (pintype "bidirectional"))
    )
    (net (code "113") (name "unconnected-(Q1-S-PadB1)") (class "Default")
      (node (ref "Q1") (pin "B1") (pinfunction "S_B1") (pintype "bidirectional"))
    )
    (net (code "114") (name "unconnected-(S1-Pad1)") (class "Default")
      (node (ref "S1") (pin "1") (pinfunction "1_1") (pintype "passive"))
    )
    (net (code "115") (name "unconnected-(VR1-NC1-Pad5)") (class "Default")
      (node (ref "VR1") (pin "5") (pinfunction "NC1_5") (pintype "bidirectional"))
    )
    (net (code "116") (name "unconnected-(VR1-NC2-Pad11)") (class "Default")
      (node (ref "VR1") (pin "11") (pinfunction "NC2_11") (pintype "bidirectional"))
    )
    (net (code "117") (name "unconnected-(XA1-P18-UNUSED-PadP18)") (class "Default")
      (node (ref "XA1") (pin "P18") (pinfunction "P18-UNUSED_P18") (pintype "bidirectional"))
    )
    (net (code "118") (name "unconnected-(XA1-P19-UNUSED-PadP19)") (class "Default")
      (node (ref "XA1") (pin "P19") (pinfunction "P19-UNUSED_P19") (pintype "bidirectional"))
    )
    (net (code "119") (name "unconnected-(XA1-P20-AP4_USB0_P-PadP20)") (class "Default")
      (node (ref "XA1") (pin "P20") (pinfunction "P20-AP4_USB0_P_P20") (pintype "bidirectional"))
    )
    (net (code "120") (name "unconnected-(XA1-P21-AP4_USB0_N-PadP21)") (class "Default")
      (node (ref "XA1") (pin "P21") (pinfunction "P21-AP4_USB0_N_P21") (pintype "bidirectional"))
    )
    (net (code "121") (name "unconnected-(XA1-P25-UNUSED-PadP25)") (class "Default")
      (node (ref "XA1") (pin "P25") (pinfunction "P25-UNUSED_P25") (pintype "bidirectional"))
    )
    (net (code "122") (name "unconnected-(XA1-P26-AP4_VDDUSB_0P9-PadP26)") (class "Default")
      (node (ref "XA1") (pin "P26") (pinfunction "P26-AP4_VDDUSB_0P9_P26") (pintype "bidirectional"))
    )
    (net (code "123") (name "unconnected-(XA1-P27-AP4-VDDUSB_3P3-PadP27)") (class "Default")
      (node (ref "XA1") (pin "P27") (pinfunction "P27-AP4-VDDUSB_3P3_P27") (pintype "bidirectional"))
    )
    (net (code "124") (name "unconnected-(XA1-P28_AP4_VDDMIPI_1P8-PadP28)") (class "Default")
      (node (ref "XA1") (pin "P28") (pinfunction "P28_AP4_VDDMIPI_1P8_P28") (pintype "bidirectional"))
    )
    (net (code "125") (name "unconnected-(XA1-P38-AP4_~{RESET}-PadP38)") (class "Default")
      (node (ref "XA1") (pin "P38") (pinfunction "P38-AP4_~{RESET}_P38") (pintype "bidirectional"))
    )
    (net (code "126") (name "unconnected-(XA1-P39-UNUSED-PadP39)") (class "Default")
      (node (ref "XA1") (pin "P39") (pinfunction "P39-UNUSED_P39") (pintype "bidirectional"))
    )
    (net (code "127") (name "unconnected-(XJ1-SBU1-PadA8)") (class "Default")
      (node (ref "XJ1") (pin "A8") (pinfunction "SBU1_A8") (pintype "bidirectional"))
    )
    (net (code "128") (name "unconnected-(XJ1-SBU2-PadB8)") (class "Default")
      (node (ref "XJ1") (pin "B8") (pinfunction "SBU2_B8") (pintype "bidirectional"))
    )
    (net (code "129") (name "~{AD_EN}") (class "Default")
      (node (ref "Q1") (pin "A1") (pinfunction "G1_A1") (pintype "input"))
      (node (ref "Q1") (pin "C1") (pinfunction "G2_C1") (pintype "input"))
      (node (ref "U4") (pin "8") (pinfunction "~{AD-EN}_8") (pintype "bidirectional"))
    )
    (net (code "130") (name "~{CHG}") (class "Default")
      (node (ref "U3") (pin "8") (pinfunction "~{CHG}_8") (pintype "bidirectional"))
      (node (ref "U4") (pin "7") (pinfunction "~{CHG}_7") (pintype "bidirectional"))
      (node (ref "XA1") (pin "P2") (pinfunction "P2-AP4_GP58/TT_~{CHG}_P2") (pintype "bidirectional"))
    )
    (net (code "131") (name "~{DW_RST}") (class "Default")
      (node (ref "U2") (pin "33") (pinfunction "~{RST}_33") (pintype "bidirectional"))
      (node (ref "XA1") (pin "P43") (pinfunction "P43-AP4_GP50/TT_~{DW_RESET}_P43") (pintype "bidirectional"))
    )
    (net (code "132") (name "~{DW_SPI_CS}") (class "Default")
      (node (ref "U2") (pin "37") (pinfunction "~{SPICS}_37") (pintype "bidirectional"))
      (node (ref "XA1") (pin "P1") (pinfunction "P1-AP4_GP29/TT_~{DW_SPI_CS}_P1") (pintype "bidirectional"))
    )
    (net (code "133") (name "~{PG}") (class "Default")
      (node (ref "U3") (pin "5") (pinfunction "~{PG}_5") (pintype "bidirectional"))
      (node (ref "XA1") (pin "P3") (pinfunction "P3-AP4_GP60/TT_~{PG}_P3") (pintype "bidirectional"))
    )
  )
)
